# Strampler_redesign_v2_2.net
KiCad netlist of a schematic drawn in EAGLE
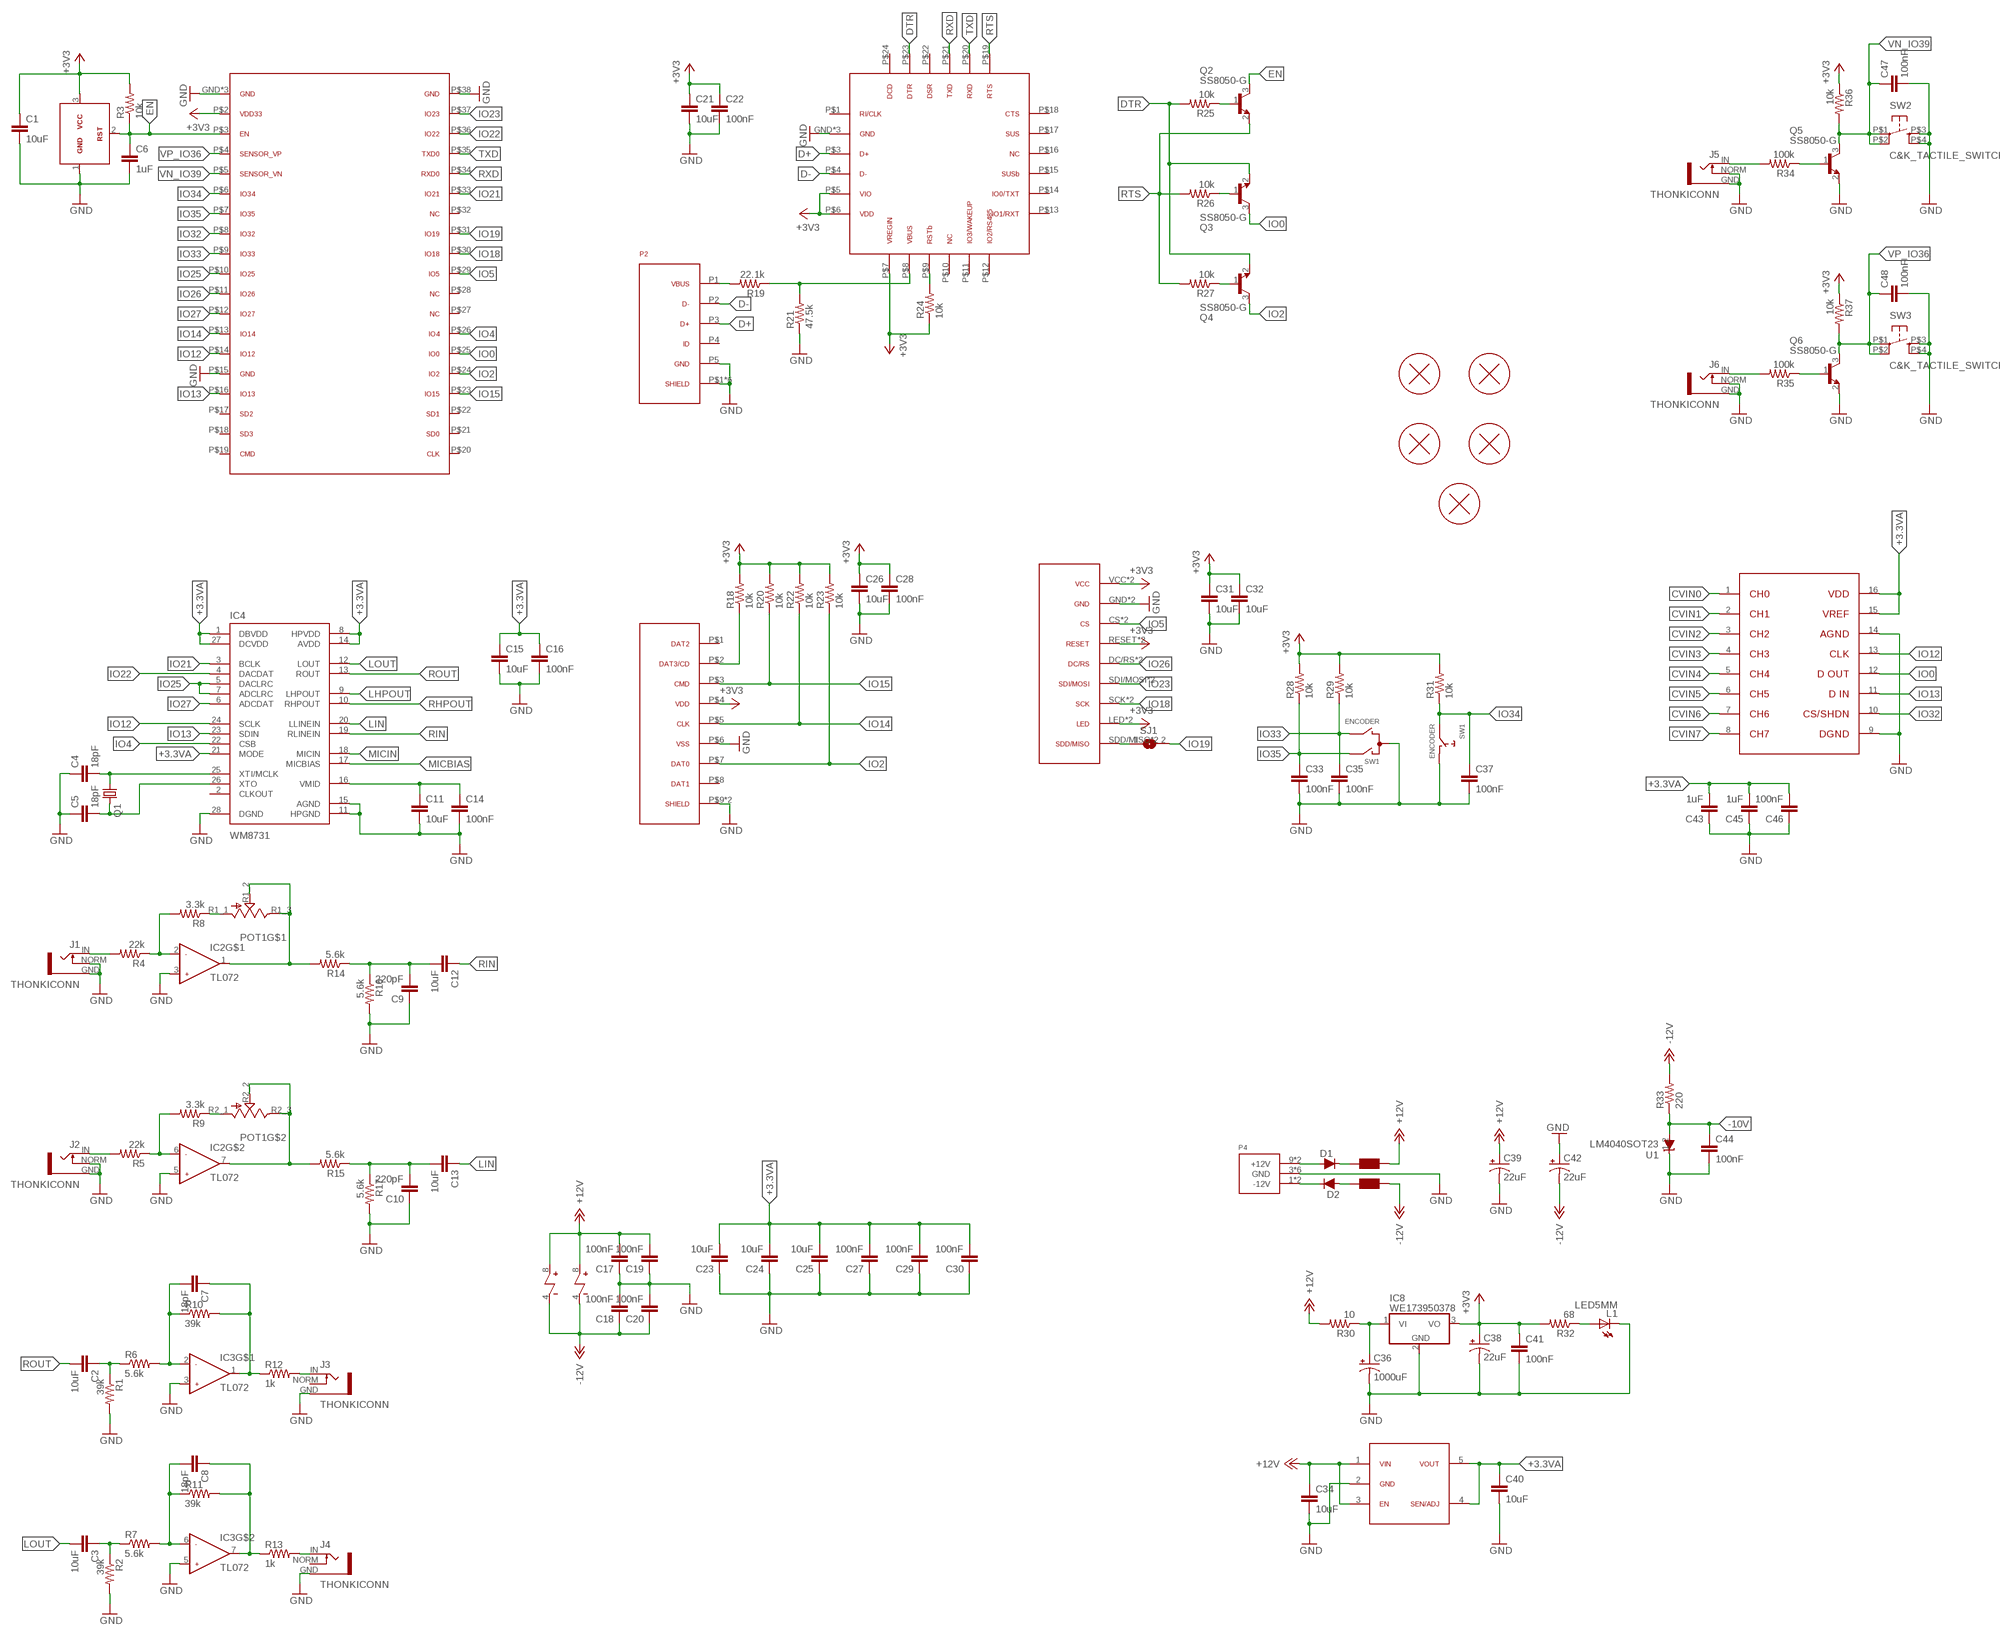
[diagram p0: schematic, sheet 1, part 1 of 2]
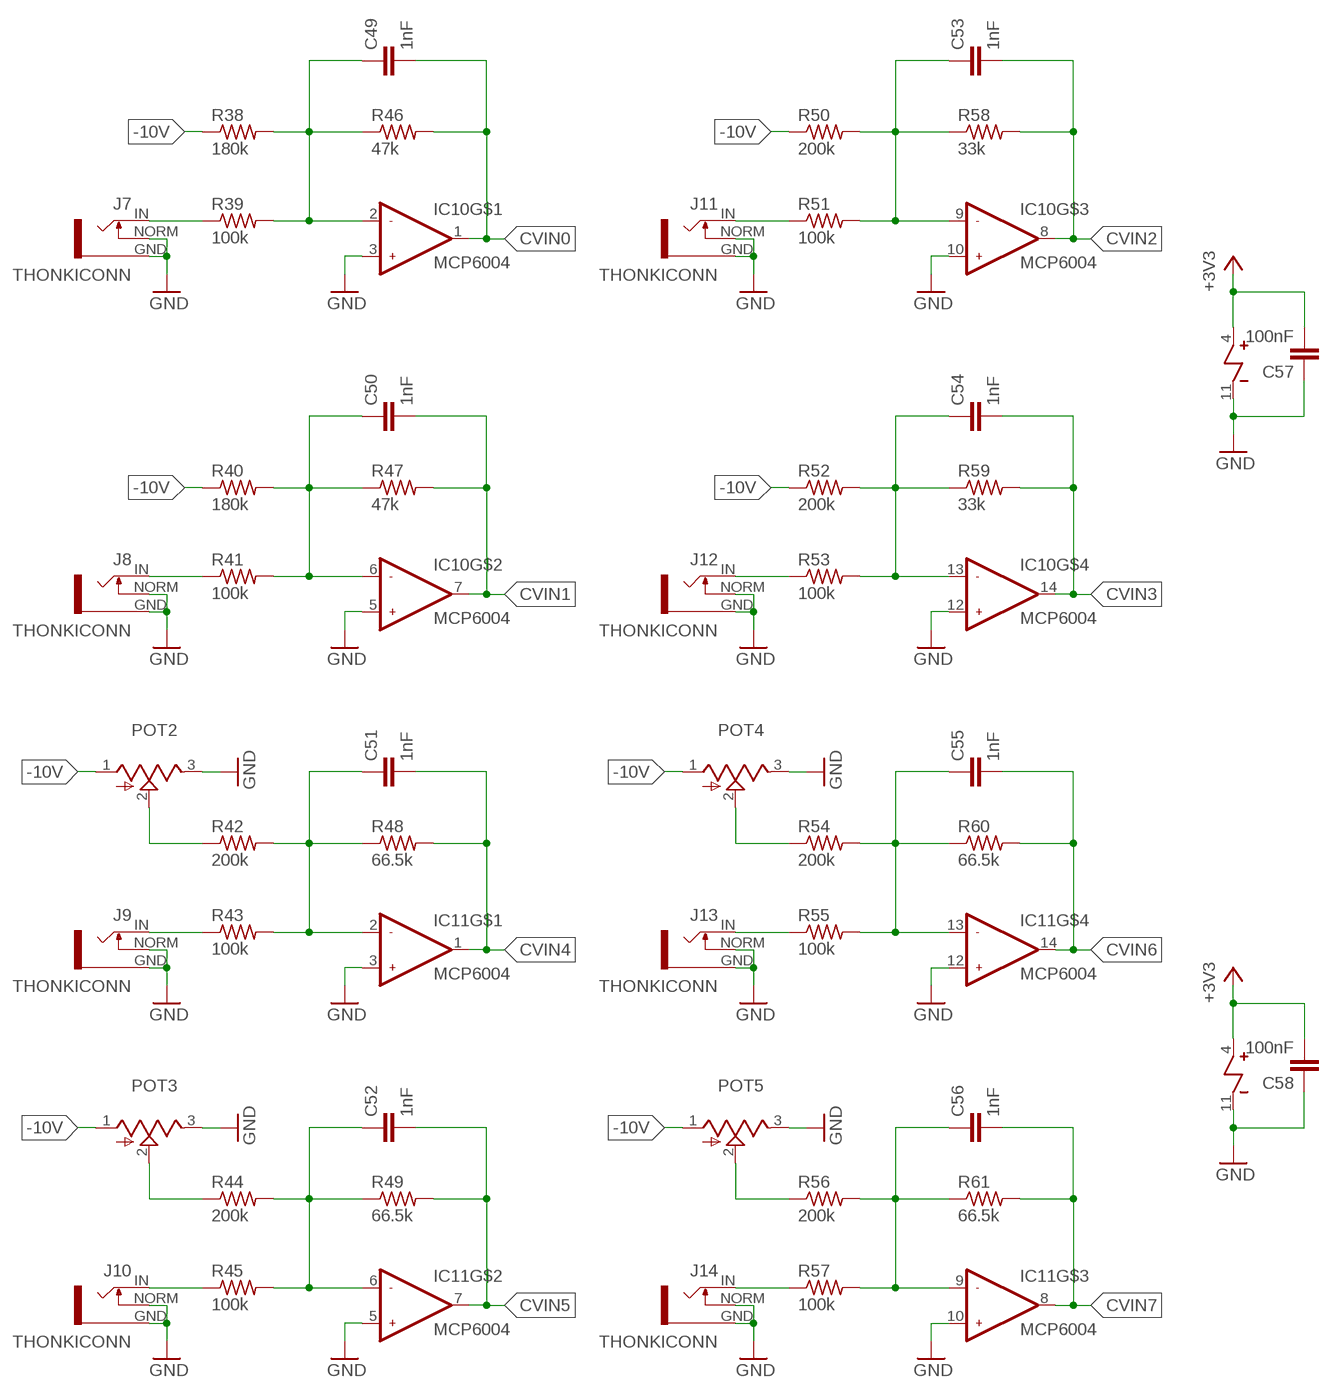
[diagram p1: schematic, sheet 1, part 2 of 2]

(export (version "E")
  (design (tool "Eeschema 10.0.6"))
  (components
    (comp (ref "C1")
      (value "10uF")
      (footprint "eagle-import:R0805")
      (libsource (lib "eagle-import") (part "CAPACITOR0805"))
    )
    (comp (ref "C2")
      (value "10uF")
      (footprint "eagle-import:R0805")
      (libsource (lib "eagle-import") (part "CAPACITOR0805"))
    )
    (comp (ref "C3")
      (value "10uF")
      (footprint "eagle-import:R0805")
      (libsource (lib "eagle-import") (part "CAPACITOR0805"))
    )
    (comp (ref "C4")
      (value "18pF")
      (footprint "eagle-import:RESISTOR_0603")
      (libsource (lib "eagle-import") (part "CAPACITOR"))
    )
    (comp (ref "C5")
      (value "18pF")
      (footprint "eagle-import:RESISTOR_0603")
      (libsource (lib "eagle-import") (part "CAPACITOR"))
    )
    (comp (ref "C6")
      (value "1uF")
      (footprint "eagle-import:RESISTOR_0603")
      (libsource (lib "eagle-import") (part "CAPACITOR"))
    )
    (comp (ref "C7")
      (value "18pF")
      (footprint "eagle-import:RESISTOR_0603")
      (libsource (lib "eagle-import") (part "CAPACITOR"))
    )
    (comp (ref "C8")
      (value "18pF")
      (footprint "eagle-import:RESISTOR_0603")
      (libsource (lib "eagle-import") (part "CAPACITOR"))
    )
    (comp (ref "C9")
      (value "220pF")
      (footprint "eagle-import:RESISTOR_0603")
      (libsource (lib "eagle-import") (part "CAPACITOR"))
    )
    (comp (ref "C10")
      (value "220pF")
      (footprint "eagle-import:RESISTOR_0603")
      (libsource (lib "eagle-import") (part "CAPACITOR"))
    )
    (comp (ref "C11")
      (value "10uF")
      (footprint "eagle-import:R0805")
      (libsource (lib "eagle-import") (part "CAPACITOR0805"))
    )
    (comp (ref "C12")
      (value "10uF")
      (footprint "eagle-import:R0805")
      (libsource (lib "eagle-import") (part "CAPACITOR0805"))
    )
    (comp (ref "C13")
      (value "10uF")
      (footprint "eagle-import:R0805")
      (libsource (lib "eagle-import") (part "CAPACITOR0805"))
    )
    (comp (ref "C14")
      (value "100nF")
      (footprint "eagle-import:RESISTOR_0603")
      (libsource (lib "eagle-import") (part "CAPACITOR"))
    )
    (comp (ref "C15")
      (value "10uF")
      (footprint "eagle-import:R0805")
      (libsource (lib "eagle-import") (part "CAPACITOR0805"))
    )
    (comp (ref "C16")
      (value "100nF")
      (footprint "eagle-import:RESISTOR_0603")
      (libsource (lib "eagle-import") (part "CAPACITOR"))
    )
    (comp (ref "C17")
      (value "100nF")
      (footprint "eagle-import:RESISTOR_0603")
      (libsource (lib "eagle-import") (part "CAPACITOR"))
    )
    (comp (ref "C18")
      (value "100nF")
      (footprint "eagle-import:RESISTOR_0603")
      (libsource (lib "eagle-import") (part "CAPACITOR"))
    )
    (comp (ref "C19")
      (value "100nF")
      (footprint "eagle-import:RESISTOR_0603")
      (libsource (lib "eagle-import") (part "CAPACITOR"))
    )
    (comp (ref "C20")
      (value "100nF")
      (footprint "eagle-import:RESISTOR_0603")
      (libsource (lib "eagle-import") (part "CAPACITOR"))
    )
    (comp (ref "C21")
      (value "10uF")
      (footprint "eagle-import:R0805")
      (libsource (lib "eagle-import") (part "CAPACITOR0805"))
    )
    (comp (ref "C22")
      (value "100nF")
      (footprint "eagle-import:RESISTOR_0603")
      (libsource (lib "eagle-import") (part "CAPACITOR"))
    )
    (comp (ref "C23")
      (value "10uF")
      (footprint "eagle-import:R0805")
      (libsource (lib "eagle-import") (part "CAPACITOR0805"))
    )
    (comp (ref "C24")
      (value "10uF")
      (footprint "eagle-import:R0805")
      (libsource (lib "eagle-import") (part "CAPACITOR0805"))
    )
    (comp (ref "C25")
      (value "10uF")
      (footprint "eagle-import:R0805")
      (libsource (lib "eagle-import") (part "CAPACITOR0805"))
    )
    (comp (ref "C26")
      (value "10uF")
      (footprint "eagle-import:R0805")
      (libsource (lib "eagle-import") (part "CAPACITOR0805"))
    )
    (comp (ref "C27")
      (value "100nF")
      (footprint "eagle-import:RESISTOR_0603")
      (libsource (lib "eagle-import") (part "CAPACITOR"))
    )
    (comp (ref "C28")
      (value "100nF")
      (footprint "eagle-import:RESISTOR_0603")
      (libsource (lib "eagle-import") (part "CAPACITOR"))
    )
    (comp (ref "C29")
      (value "100nF")
      (footprint "eagle-import:RESISTOR_0603")
      (libsource (lib "eagle-import") (part "CAPACITOR"))
    )
    (comp (ref "C30")
      (value "100nF")
      (footprint "eagle-import:RESISTOR_0603")
      (libsource (lib "eagle-import") (part "CAPACITOR"))
    )
    (comp (ref "C31")
      (value "10uF")
      (footprint "eagle-import:R0805")
      (libsource (lib "eagle-import") (part "CAPACITOR0805"))
    )
    (comp (ref "C32")
      (value "10uF")
      (footprint "eagle-import:R0805")
      (libsource (lib "eagle-import") (part "CAPACITOR0805"))
    )
    (comp (ref "C33")
      (value "100nF")
      (footprint "eagle-import:RESISTOR_0603")
      (libsource (lib "eagle-import") (part "CAPACITOR"))
    )
    (comp (ref "C34")
      (value "10uF")
      (footprint "eagle-import:R1210")
      (libsource (lib "eagle-import") (part "CAPACITOR1210"))
    )
    (comp (ref "C35")
      (value "100nF")
      (footprint "eagle-import:RESISTOR_0603")
      (libsource (lib "eagle-import") (part "CAPACITOR"))
    )
    (comp (ref "C36")
      (value "1000uF")
      (footprint "eagle-import:PANASONIC_G")
      (libsource (lib "eagle-import") (part "CAP_POLG"))
    )
    (comp (ref "C37")
      (value "100nF")
      (footprint "eagle-import:RESISTOR_0603")
      (libsource (lib "eagle-import") (part "CAPACITOR"))
    )
    (comp (ref "C38")
      (value "22uF")
      (footprint "eagle-import:1206_POL")
      (libsource (lib "eagle-import") (part "CAP_POL1206_TANT"))
    )
    (comp (ref "C39")
      (value "22uF")
      (footprint "eagle-import:1206_POL")
      (libsource (lib "eagle-import") (part "CAP_POL1206_TANT"))
    )
    (comp (ref "C40")
      (value "10uF")
      (footprint "eagle-import:R0805")
      (libsource (lib "eagle-import") (part "CAPACITOR0805"))
    )
    (comp (ref "C41")
      (value "100nF")
      (footprint "eagle-import:RESISTOR_0603")
      (libsource (lib "eagle-import") (part "CAPACITOR"))
    )
    (comp (ref "C42")
      (value "22uF")
      (footprint "eagle-import:1206_POL")
      (libsource (lib "eagle-import") (part "CAP_POL1206_TANT"))
    )
    (comp (ref "C43")
      (value "1uF")
      (footprint "eagle-import:RESISTOR_0603")
      (libsource (lib "eagle-import") (part "CAPACITOR"))
    )
    (comp (ref "C44")
      (value "100nF")
      (footprint "eagle-import:RESISTOR_0603")
      (libsource (lib "eagle-import") (part "CAPACITOR"))
    )
    (comp (ref "C45")
      (value "1uF")
      (footprint "eagle-import:RESISTOR_0603")
      (libsource (lib "eagle-import") (part "CAPACITOR"))
    )
    (comp (ref "C46")
      (value "100nF")
      (footprint "eagle-import:RESISTOR_0603")
      (libsource (lib "eagle-import") (part "CAPACITOR"))
    )
    (comp (ref "C47")
      (value "100nF")
      (footprint "eagle-import:RESISTOR_0603")
      (libsource (lib "eagle-import") (part "CAPACITOR"))
    )
    (comp (ref "C48")
      (value "100nF")
      (footprint "eagle-import:RESISTOR_0603")
      (libsource (lib "eagle-import") (part "CAPACITOR"))
    )
    (comp (ref "C49")
      (value "1nF")
      (footprint "eagle-import:RESISTOR_0603")
      (libsource (lib "eagle-import") (part "CAPACITOR"))
    )
    (comp (ref "C50")
      (value "1nF")
      (footprint "eagle-import:RESISTOR_0603")
      (libsource (lib "eagle-import") (part "CAPACITOR"))
    )
    (comp (ref "C51")
      (value "1nF")
      (footprint "eagle-import:RESISTOR_0603")
      (libsource (lib "eagle-import") (part "CAPACITOR"))
    )
    (comp (ref "C52")
      (value "1nF")
      (footprint "eagle-import:RESISTOR_0603")
      (libsource (lib "eagle-import") (part "CAPACITOR"))
    )
    (comp (ref "C53")
      (value "1nF")
      (footprint "eagle-import:RESISTOR_0603")
      (libsource (lib "eagle-import") (part "CAPACITOR"))
    )
    (comp (ref "C54")
      (value "1nF")
      (footprint "eagle-import:RESISTOR_0603")
      (libsource (lib "eagle-import") (part "CAPACITOR"))
    )
    (comp (ref "C55")
      (value "1nF")
      (footprint "eagle-import:RESISTOR_0603")
      (libsource (lib "eagle-import") (part "CAPACITOR"))
    )
    (comp (ref "C56")
      (value "1nF")
      (footprint "eagle-import:RESISTOR_0603")
      (libsource (lib "eagle-import") (part "CAPACITOR"))
    )
    (comp (ref "C57")
      (value "100nF")
      (footprint "eagle-import:RESISTOR_0603")
      (libsource (lib "eagle-import") (part "CAPACITOR"))
    )
    (comp (ref "C58")
      (value "100nF")
      (footprint "eagle-import:RESISTOR_0603")
      (libsource (lib "eagle-import") (part "CAPACITOR"))
    )
    (comp (ref "D1")
      (value "DIODE")
      (footprint "eagle-import:SOD123")
      (libsource (lib "eagle-import") (part "DIODE"))
    )
    (comp (ref "D2")
      (value "DIODE")
      (footprint "eagle-import:SOD123")
      (libsource (lib "eagle-import") (part "DIODE"))
    )
    (comp (ref "F1")
      (value "FERRITE-BEAD0805")
      (footprint "eagle-import:R0805")
      (libsource (lib "eagle-import") (part "FERRITE-BEAD0805"))
    )
    (comp (ref "F2")
      (value "FERRITE-BEAD0805")
      (footprint "eagle-import:R0805")
      (libsource (lib "eagle-import") (part "FERRITE-BEAD0805"))
    )
    (comp (ref "H1")
      (value "PCB_SCREW")
      (footprint "eagle-import:PCB_SCREW")
      (libsource (lib "eagle-import") (part "PCB_SCREW"))
    )
    (comp (ref "H2")
      (value "PCB_SCREW")
      (footprint "eagle-import:PCB_SCREW")
      (libsource (lib "eagle-import") (part "PCB_SCREW"))
    )
    (comp (ref "H3")
      (value "PCB_SCREW")
      (footprint "eagle-import:PCB_SCREW")
      (libsource (lib "eagle-import") (part "PCB_SCREW"))
    )
    (comp (ref "H4")
      (value "PCB_SCREW")
      (footprint "eagle-import:PCB_SCREW")
      (libsource (lib "eagle-import") (part "PCB_SCREW"))
    )
    (comp (ref "H5")
      (value "PCB_SCREW")
      (footprint "eagle-import:PCB_SCREW")
      (libsource (lib "eagle-import") (part "PCB_SCREW"))
    )
    (comp (ref "IC1")
      (value "MIC803")
      (footprint "eagle-import:SOT23")
      (libsource (lib "eagle-import") (part "MIC803"))
    )
    (comp (ref "IC2")
      (value "TL072")
      (footprint "eagle-import:SOIC8")
      (libsource (lib "eagle-import") (part "OPAMP_DUAL"))
    )
    (comp (ref "IC3")
      (value "TL072")
      (footprint "eagle-import:SOIC8")
      (libsource (lib "eagle-import") (part "OPAMP_DUAL"))
    )
    (comp (ref "IC4")
      (value "WM8731")
      (footprint "eagle-import:SSOP28")
      (libsource (lib "eagle-import") (part "WM8731"))
    )
    (comp (ref "IC5")
      (value "ESP32-WROVER-B")
      (footprint "eagle-import:ESP32-WROVER-B")
      (libsource (lib "eagle-import") (part "ESP32-WROVER-B"))
    )
    (comp (ref "IC6")
      (value "CP2102N")
      (footprint "eagle-import:CP2102N")
      (libsource (lib "eagle-import") (part "CP2102N"))
    )
    (comp (ref "IC7")
      (value "ADP7118")
      (footprint "eagle-import:SOT23-5L")
      (libsource (lib "eagle-import") (part "ADP7118"))
    )
    (comp (ref "IC8")
      (value "WE173950378")
      (footprint "eagle-import:WE78")
      (libsource (lib "eagle-import") (part "WE173950378"))
    )
    (comp (ref "IC9")
      (value "MCP3208")
      (footprint "eagle-import:SOIC16")
      (libsource (lib "eagle-import") (part "MCP3208"))
    )
    (comp (ref "IC10")
      (value "MCP6004")
      (footprint "eagle-import:TSSOP14")
      (libsource (lib "eagle-import") (part "OPAMP_QUADPWR"))
    )
    (comp (ref "IC11")
      (value "MCP6004")
      (footprint "eagle-import:TSSOP14")
      (libsource (lib "eagle-import") (part "OPAMP_QUADPWR"))
    )
    (comp (ref "J1")
      (value "THONKICONN")
      (footprint "eagle-import:PROTOJACK")
      (libsource (lib "eagle-import") (part "THONKICONN"))
    )
    (comp (ref "J2")
      (value "THONKICONN")
      (footprint "eagle-import:PROTOJACK")
      (libsource (lib "eagle-import") (part "THONKICONN"))
    )
    (comp (ref "J3")
      (value "THONKICONN")
      (footprint "eagle-import:PROTOJACK")
      (libsource (lib "eagle-import") (part "THONKICONN"))
    )
    (comp (ref "J4")
      (value "THONKICONN")
      (footprint "eagle-import:PROTOJACK")
      (libsource (lib "eagle-import") (part "THONKICONN"))
    )
    (comp (ref "J5")
      (value "THONKICONN")
      (footprint "eagle-import:PROTOJACK")
      (libsource (lib "eagle-import") (part "THONKICONN"))
    )
    (comp (ref "J6")
      (value "THONKICONN")
      (footprint "eagle-import:PROTOJACK")
      (libsource (lib "eagle-import") (part "THONKICONN"))
    )
    (comp (ref "J7")
      (value "THONKICONN")
      (footprint "eagle-import:PROTOJACK")
      (libsource (lib "eagle-import") (part "THONKICONN"))
    )
    (comp (ref "J8")
      (value "THONKICONN")
      (footprint "eagle-import:PROTOJACK")
      (libsource (lib "eagle-import") (part "THONKICONN"))
    )
    (comp (ref "J9")
      (value "THONKICONN")
      (footprint "eagle-import:PROTOJACK")
      (libsource (lib "eagle-import") (part "THONKICONN"))
    )
    (comp (ref "J10")
      (value "THONKICONN")
      (footprint "eagle-import:PROTOJACK")
      (libsource (lib "eagle-import") (part "THONKICONN"))
    )
    (comp (ref "J11")
      (value "THONKICONN")
      (footprint "eagle-import:PROTOJACK")
      (libsource (lib "eagle-import") (part "THONKICONN"))
    )
    (comp (ref "J12")
      (value "THONKICONN")
      (footprint "eagle-import:PROTOJACK")
      (libsource (lib "eagle-import") (part "THONKICONN"))
    )
    (comp (ref "J13")
      (value "THONKICONN")
      (footprint "eagle-import:PROTOJACK")
      (libsource (lib "eagle-import") (part "THONKICONN"))
    )
    (comp (ref "J14")
      (value "THONKICONN")
      (footprint "eagle-import:PROTOJACK")
      (libsource (lib "eagle-import") (part "THONKICONN"))
    )
    (comp (ref "L1")
      (value "LED5MM")
      (footprint "eagle-import:LED_5MM")
      (libsource (lib "eagle-import") (part "LED5MM"))
    )
    (comp (ref "P1")
      (value "SD-CARD")
      (footprint "eagle-import:SD-CARD-THONK")
      (libsource (lib "eagle-import") (part "SD-CARD"))
    )
    (comp (ref "P2")
      (value "USB-B")
      (footprint "eagle-import:USB-B-MOLEX-1050170001")
      (libsource (lib "eagle-import") (part "USB-B"))
    )
    (comp (ref "P3")
      (value "MSP2202_DISPLAY")
      (footprint "eagle-import:MSP2202_DISPLAY")
      (libsource (lib "eagle-import") (part "MSP2202_DISPLAY"))
    )
    (comp (ref "P4")
      (value "POWER_SIMPLE10")
      (footprint "eagle-import:POWER_10")
      (libsource (lib "eagle-import") (part "POWER_SIMPLE10"))
    )
    (comp (ref "POT1")
      (value "POT_DUAL_THONK")
      (footprint "eagle-import:POT_DUAL_THONK")
      (libsource (lib "eagle-import") (part "POT_DUAL_THONK"))
    )
    (comp (ref "POT2")
      (value "POT_VERTICAL")
      (footprint "eagle-import:ALPS_POT_VERTICAL")
      (libsource (lib "eagle-import") (part "POT_VERTICAL"))
    )
    (comp (ref "POT3")
      (value "POT_VERTICAL")
      (footprint "eagle-import:ALPS_POT_VERTICAL")
      (libsource (lib "eagle-import") (part "POT_VERTICAL"))
    )
    (comp (ref "POT4")
      (value "POT_VERTICAL")
      (footprint "eagle-import:ALPS_POT_VERTICAL")
      (libsource (lib "eagle-import") (part "POT_VERTICAL"))
    )
    (comp (ref "POT5")
      (value "POT_VERTICAL")
      (footprint "eagle-import:ALPS_POT_VERTICAL")
      (libsource (lib "eagle-import") (part "POT_VERTICAL"))
    )
    (comp (ref "Q1")
      (value "CRYSTAL")
      (footprint "eagle-import:HC49UP")
      (libsource (lib "eagle-import") (part "CRYSTAL"))
    )
    (comp (ref "Q2")
      (value "SS8050-G")
      (footprint "eagle-import:SOT23")
      (libsource (lib "eagle-import") (part "MMBT3904SOT23"))
    )
    (comp (ref "Q3")
      (value "SS8050-G")
      (footprint "eagle-import:SOT23")
      (libsource (lib "eagle-import") (part "MMBT3904SOT23"))
    )
    (comp (ref "Q4")
      (value "SS8050-G")
      (footprint "eagle-import:SOT23")
      (libsource (lib "eagle-import") (part "MMBT3904SOT23"))
    )
    (comp (ref "Q5")
      (value "SS8050-G")
      (footprint "eagle-import:SOT23")
      (libsource (lib "eagle-import") (part "MMBT3904SOT23"))
    )
    (comp (ref "Q6")
      (value "SS8050-G")
      (footprint "eagle-import:SOT23")
      (libsource (lib "eagle-import") (part "MMBT3904SOT23"))
    )
    (comp (ref "R1")
      (value "39k")
      (footprint "eagle-import:RESISTOR_0603")
      (libsource (lib "eagle-import") (part "RESISTOR"))
    )
    (comp (ref "R2")
      (value "39k")
      (footprint "eagle-import:RESISTOR_0603")
      (libsource (lib "eagle-import") (part "RESISTOR"))
    )
    (comp (ref "R3")
      (value "10k")
      (footprint "eagle-import:RESISTOR_0603")
      (libsource (lib "eagle-import") (part "RESISTOR"))
    )
    (comp (ref "R4")
      (value "22k")
      (footprint "eagle-import:RESISTOR_0603")
      (libsource (lib "eagle-import") (part "RESISTOR"))
    )
    (comp (ref "R5")
      (value "22k")
      (footprint "eagle-import:RESISTOR_0603")
      (libsource (lib "eagle-import") (part "RESISTOR"))
    )
    (comp (ref "R6")
      (value "5.6k")
      (footprint "eagle-import:RESISTOR_0603")
      (libsource (lib "eagle-import") (part "RESISTOR"))
    )
    (comp (ref "R7")
      (value "5.6k")
      (footprint "eagle-import:RESISTOR_0603")
      (libsource (lib "eagle-import") (part "RESISTOR"))
    )
    (comp (ref "R8")
      (value "3.3k")
      (footprint "eagle-import:RESISTOR_0603")
      (libsource (lib "eagle-import") (part "RESISTOR"))
    )
    (comp (ref "R9")
      (value "3.3k")
      (footprint "eagle-import:RESISTOR_0603")
      (libsource (lib "eagle-import") (part "RESISTOR"))
    )
    (comp (ref "R10")
      (value "39k")
      (footprint "eagle-import:RESISTOR_0603")
      (libsource (lib "eagle-import") (part "RESISTOR"))
    )
    (comp (ref "R11")
      (value "39k")
      (footprint "eagle-import:RESISTOR_0603")
      (libsource (lib "eagle-import") (part "RESISTOR"))
    )
    (comp (ref "R12")
      (value "1k")
      (footprint "eagle-import:RESISTOR_0603")
      (libsource (lib "eagle-import") (part "RESISTOR"))
    )
    (comp (ref "R13")
      (value "1k")
      (footprint "eagle-import:RESISTOR_0603")
      (libsource (lib "eagle-import") (part "RESISTOR"))
    )
    (comp (ref "R14")
      (value "5.6k")
      (footprint "eagle-import:RESISTOR_0603")
      (libsource (lib "eagle-import") (part "RESISTOR"))
    )
    (comp (ref "R15")
      (value "5.6k")
      (footprint "eagle-import:RESISTOR_0603")
      (libsource (lib "eagle-import") (part "RESISTOR"))
    )
    (comp (ref "R16")
      (value "5.6k")
      (footprint "eagle-import:RESISTOR_0603")
      (libsource (lib "eagle-import") (part "RESISTOR"))
    )
    (comp (ref "R17")
      (value "5.6k")
      (footprint "eagle-import:RESISTOR_0603")
      (libsource (lib "eagle-import") (part "RESISTOR"))
    )
    (comp (ref "R18")
      (value "10k")
      (footprint "eagle-import:RESISTOR_0603")
      (libsource (lib "eagle-import") (part "RESISTOR"))
    )
    (comp (ref "R19")
      (value "22.1k")
      (footprint "eagle-import:RESISTOR_0603")
      (libsource (lib "eagle-import") (part "RESISTOR"))
    )
    (comp (ref "R20")
      (value "10k")
      (footprint "eagle-import:RESISTOR_0603")
      (libsource (lib "eagle-import") (part "RESISTOR"))
    )
    (comp (ref "R21")
      (value "47.5k")
      (footprint "eagle-import:RESISTOR_0603")
      (libsource (lib "eagle-import") (part "RESISTOR"))
    )
    (comp (ref "R22")
      (value "10k")
      (footprint "eagle-import:RESISTOR_0603")
      (libsource (lib "eagle-import") (part "RESISTOR"))
    )
    (comp (ref "R23")
      (value "10k")
      (footprint "eagle-import:RESISTOR_0603")
      (libsource (lib "eagle-import") (part "RESISTOR"))
    )
    (comp (ref "R24")
      (value "10k")
      (footprint "eagle-import:RESISTOR_0603")
      (libsource (lib "eagle-import") (part "RESISTOR"))
    )
    (comp (ref "R25")
      (value "10k")
      (footprint "eagle-import:RESISTOR_0603")
      (libsource (lib "eagle-import") (part "RESISTOR"))
    )
    (comp (ref "R26")
      (value "10k")
      (footprint "eagle-import:RESISTOR_0603")
      (libsource (lib "eagle-import") (part "RESISTOR"))
    )
    (comp (ref "R27")
      (value "10k")
      (footprint "eagle-import:RESISTOR_0603")
      (libsource (lib "eagle-import") (part "RESISTOR"))
    )
    (comp (ref "R28")
      (value "10k")
      (footprint "eagle-import:RESISTOR_0603")
      (libsource (lib "eagle-import") (part "RESISTOR"))
    )
    (comp (ref "R29")
      (value "10k")
      (footprint "eagle-import:RESISTOR_0603")
      (libsource (lib "eagle-import") (part "RESISTOR"))
    )
    (comp (ref "R30")
      (value "10")
      (footprint "eagle-import:R2512")
      (libsource (lib "eagle-import") (part "RESISTOR2512"))
    )
    (comp (ref "R31")
      (value "10k")
      (footprint "eagle-import:RESISTOR_0603")
      (libsource (lib "eagle-import") (part "RESISTOR"))
    )
    (comp (ref "R32")
      (value "68")
      (footprint "eagle-import:RESISTOR_0603")
      (libsource (lib "eagle-import") (part "RESISTOR"))
    )
    (comp (ref "R33")
      (value "220")
      (footprint "eagle-import:RESISTOR_0603")
      (libsource (lib "eagle-import") (part "RESISTOR"))
    )
    (comp (ref "R34")
      (value "100k")
      (footprint "eagle-import:RESISTOR_0603")
      (libsource (lib "eagle-import") (part "RESISTOR"))
    )
    (comp (ref "R35")
      (value "100k")
      (footprint "eagle-import:RESISTOR_0603")
      (libsource (lib "eagle-import") (part "RESISTOR"))
    )
    (comp (ref "R36")
      (value "10k")
      (footprint "eagle-import:RESISTOR_0603")
      (libsource (lib "eagle-import") (part "RESISTOR"))
    )
    (comp (ref "R37")
      (value "10k")
      (footprint "eagle-import:RESISTOR_0603")
      (libsource (lib "eagle-import") (part "RESISTOR"))
    )
    (comp (ref "R38")
      (value "180k")
      (footprint "eagle-import:RESISTOR_0603")
      (libsource (lib "eagle-import") (part "RESISTOR"))
    )
    (comp (ref "R39")
      (value "100k")
      (footprint "eagle-import:RESISTOR_0603")
      (libsource (lib "eagle-import") (part "RESISTOR"))
    )
    (comp (ref "R40")
      (value "180k")
      (footprint "eagle-import:RESISTOR_0603")
      (libsource (lib "eagle-import") (part "RESISTOR"))
    )
    (comp (ref "R41")
      (value "100k")
      (footprint "eagle-import:RESISTOR_0603")
      (libsource (lib "eagle-import") (part "RESISTOR"))
    )
    (comp (ref "R42")
      (value "200k")
      (footprint "eagle-import:RESISTOR_0603")
      (libsource (lib "eagle-import") (part "RESISTOR"))
    )
    (comp (ref "R43")
      (value "100k")
      (footprint "eagle-import:RESISTOR_0603")
      (libsource (lib "eagle-import") (part "RESISTOR"))
    )
    (comp (ref "R44")
      (value "200k")
      (footprint "eagle-import:RESISTOR_0603")
      (libsource (lib "eagle-import") (part "RESISTOR"))
    )
    (comp (ref "R45")
      (value "100k")
      (footprint "eagle-import:RESISTOR_0603")
      (libsource (lib "eagle-import") (part "RESISTOR"))
    )
    (comp (ref "R46")
      (value "47k")
      (footprint "eagle-import:RESISTOR_0603")
      (libsource (lib "eagle-import") (part "RESISTOR"))
    )
    (comp (ref "R47")
      (value "47k")
      (footprint "eagle-import:RESISTOR_0603")
      (libsource (lib "eagle-import") (part "RESISTOR"))
    )
    (comp (ref "R48")
      (value "66.5k")
      (footprint "eagle-import:RESISTOR_0603")
      (libsource (lib "eagle-import") (part "RESISTOR"))
    )
    (comp (ref "R49")
      (value "66.5k")
      (footprint "eagle-import:RESISTOR_0603")
      (libsource (lib "eagle-import") (part "RESISTOR"))
    )
    (comp (ref "R50")
      (value "200k")
      (footprint "eagle-import:RESISTOR_0603")
      (libsource (lib "eagle-import") (part "RESISTOR"))
    )
    (comp (ref "R51")
      (value "100k")
      (footprint "eagle-import:RESISTOR_0603")
      (libsource (lib "eagle-import") (part "RESISTOR"))
    )
    (comp (ref "R52")
      (value "200k")
      (footprint "eagle-import:RESISTOR_0603")
      (libsource (lib "eagle-import") (part "RESISTOR"))
    )
    (comp (ref "R53")
      (value "100k")
      (footprint "eagle-import:RESISTOR_0603")
      (libsource (lib "eagle-import") (part "RESISTOR"))
    )
    (comp (ref "R54")
      (value "200k")
      (footprint "eagle-import:RESISTOR_0603")
      (libsource (lib "eagle-import") (part "RESISTOR"))
    )
    (comp (ref "R55")
      (value "100k")
      (footprint "eagle-import:RESISTOR_0603")
      (libsource (lib "eagle-import") (part "RESISTOR"))
    )
    (comp (ref "R56")
      (value "200k")
      (footprint "eagle-import:RESISTOR_0603")
      (libsource (lib "eagle-import") (part "RESISTOR"))
    )
    (comp (ref "R57")
      (value "100k")
      (footprint "eagle-import:RESISTOR_0603")
      (libsource (lib "eagle-import") (part "RESISTOR"))
    )
    (comp (ref "R58")
      (value "33k")
      (footprint "eagle-import:RESISTOR_0603")
      (libsource (lib "eagle-import") (part "RESISTOR"))
    )
    (comp (ref "R59")
      (value "33k")
      (footprint "eagle-import:RESISTOR_0603")
      (libsource (lib "eagle-import") (part "RESISTOR"))
    )
    (comp (ref "R60")
      (value "66.5k")
      (footprint "eagle-import:RESISTOR_0603")
      (libsource (lib "eagle-import") (part "RESISTOR"))
    )
    (comp (ref "R61")
      (value "66.5k")
      (footprint "eagle-import:RESISTOR_0603")
      (libsource (lib "eagle-import") (part "RESISTOR"))
    )
    (comp (ref "SJ1") (value "SJ") (footprint "eagle-import:SJ") (libsource (lib "eagle-import") (part "SJ")))
    (comp (ref "SW1")
      (value "ENCODER")
      (footprint "eagle-import:ALPS_EC12E_SW")
      (fields (field (name "MPN") "EC12E2424407"))
      (libsource (lib "eagle-import") (part "ENCODER"))
    )
    (comp (ref "SW2")
      (value "C&K_TACTILE_SWITCH")
      (footprint "eagle-import:C&K_TACTILE_SWITCH")
      (libsource (lib "eagle-import") (part "C&K_TACTILE_SWITCH"))
    )
    (comp (ref "SW3")
      (value "C&K_TACTILE_SWITCH")
      (footprint "eagle-import:C&K_TACTILE_SWITCH")
      (libsource (lib "eagle-import") (part "C&K_TACTILE_SWITCH"))
    )
    (comp (ref "U1")
      (value "LM4040SOT23")
      (footprint "eagle-import:SOT23")
      (libsource (lib "eagle-import") (part "LM4040SOT23"))
    )
  )
  (nets
    (net (code "1") (name "+3.3VA") (class "Default")
      (node (ref "C15") (pin "1") (pinfunction "1_1") (pintype "passive"))
      (node (ref "C16") (pin "1") (pinfunction "1_1") (pintype "passive"))
      (node (ref "C23") (pin "2") (pinfunction "2_2") (pintype "passive"))
      (node (ref "C24") (pin "2") (pinfunction "2_2") (pintype "passive"))
      (node (ref "C25") (pin "2") (pinfunction "2_2") (pintype "passive"))
      (node (ref "C27") (pin "2") (pinfunction "2_2") (pintype "passive"))
      (node (ref "C29") (pin "2") (pinfunction "2_2") (pintype "passive"))
      (node (ref "C30") (pin "2") (pinfunction "2_2") (pintype "passive"))
      (node (ref "C40") (pin "1") (pinfunction "1_1") (pintype "passive"))
      (node (ref "C43") (pin "2") (pinfunction "2_2") (pintype "passive"))
      (node (ref "C45") (pin "2") (pinfunction "2_2") (pintype "passive"))
      (node (ref "C46") (pin "2") (pinfunction "2_2") (pintype "passive"))
      (node (ref "IC4") (pin "1") (pinfunction "DBVDD_1") (pintype "bidirectional"))
      (node (ref "IC4") (pin "14") (pinfunction "AVDD_14") (pintype "bidirectional"))
      (node (ref "IC4") (pin "21") (pinfunction "MODE_21") (pintype "bidirectional"))
      (node (ref "IC4") (pin "27") (pinfunction "DCVDD_27") (pintype "bidirectional"))
      (node (ref "IC4") (pin "8") (pinfunction "HPVDD_8") (pintype "bidirectional"))
      (node (ref "IC7") (pin "4") (pinfunction "P$4_4") (pintype "bidirectional"))
      (node (ref "IC7") (pin "5") (pinfunction "P$5_5") (pintype "bidirectional"))
      (node (ref "IC9") (pin "15") (pinfunction "P$15_15") (pintype "bidirectional"))
      (node (ref "IC9") (pin "16") (pinfunction "P$16_16") (pintype "bidirectional"))
    )
    (net (code "2") (name "+3V3") (class "Default")
      (node (ref "C1") (pin "1") (pinfunction "1_1") (pintype "passive"))
      (node (ref "C21") (pin "1") (pinfunction "1_1") (pintype "passive"))
      (node (ref "C22") (pin "1") (pinfunction "1_1") (pintype "passive"))
      (node (ref "C26") (pin "1") (pinfunction "1_1") (pintype "passive"))
      (node (ref "C28") (pin "1") (pinfunction "1_1") (pintype "passive"))
      (node (ref "C31") (pin "1") (pinfunction "1_1") (pintype "passive"))
      (node (ref "C32") (pin "1") (pinfunction "1_1") (pintype "passive"))
      (node (ref "C38") (pin "2") (pinfunction "+_2") (pintype "passive"))
      (node (ref "C41") (pin "1") (pinfunction "1_1") (pintype "passive"))
      (node (ref "C57") (pin "2") (pinfunction "2_2") (pintype "passive"))
      (node (ref "C58") (pin "2") (pinfunction "2_2") (pintype "passive"))
      (node (ref "IC1") (pin "3") (pinfunction "P$3_3") (pintype "bidirectional"))
      (node (ref "IC10") (pin "4") (pinfunction "P$1_4") (pintype "bidirectional"))
      (node (ref "IC11") (pin "4") (pinfunction "P$1_4") (pintype "bidirectional"))
      (node (ref "IC5") (pin "P$2") (pinfunction "P$2_P$2") (pintype "bidirectional"))
      (node (ref "IC6") (pin "P$5") (pinfunction "P$5_P$5") (pintype "bidirectional"))
      (node (ref "IC6") (pin "P$6") (pinfunction "P$6_P$6") (pintype "bidirectional"))
      (node (ref "IC6") (pin "P$7") (pinfunction "P$7_P$7") (pintype "bidirectional"))
      (node (ref "IC8") (pin "3") (pinfunction "VO_3") (pintype "passive"))
      (node (ref "P1") (pin "P$4") (pinfunction "P$4_P$4") (pintype "bidirectional"))
      (node (ref "P3") (pin "LED") (pinfunction "P$8_LED") (pintype "bidirectional"))
      (node (ref "P3") (pin "LED1") (pinfunction "P$8_LED1") (pintype "bidirectional"))
      (node (ref "P3") (pin "RESET") (pinfunction "P$4_RESET") (pintype "bidirectional"))
      (node (ref "P3") (pin "RESET1") (pinfunction "P$4_RESET1") (pintype "bidirectional"))
      (node (ref "P3") (pin "VCC") (pinfunction "P$1_VCC") (pintype "bidirectional"))
      (node (ref "P3") (pin "VCC1") (pinfunction "P$1_VCC1") (pintype "bidirectional"))
      (node (ref "R18") (pin "2") (pinfunction "2_2") (pintype "passive"))
      (node (ref "R20") (pin "2") (pinfunction "2_2") (pintype "passive"))
      (node (ref "R22") (pin "2") (pinfunction "2_2") (pintype "passive"))
      (node (ref "R23") (pin "2") (pinfunction "2_2") (pintype "passive"))
      (node (ref "R24") (pin "1") (pinfunction "1_1") (pintype "passive"))
      (node (ref "R28") (pin "2") (pinfunction "2_2") (pintype "passive"))
      (node (ref "R29") (pin "2") (pinfunction "2_2") (pintype "passive"))
      (node (ref "R3") (pin "2") (pinfunction "2_2") (pintype "passive"))
      (node (ref "R31") (pin "2") (pinfunction "2_2") (pintype "passive"))
      (node (ref "R32") (pin "2") (pinfunction "2_2") (pintype "passive"))
      (node (ref "R36") (pin "1") (pinfunction "1_1") (pintype "passive"))
      (node (ref "R37") (pin "1") (pinfunction "1_1") (pintype "passive"))
    )
    (net (code "3") (name "+12V") (class "Default")
      (node (ref "C17") (pin "2") (pinfunction "2_2") (pintype "passive"))
      (node (ref "C19") (pin "2") (pinfunction "2_2") (pintype "passive"))
      (node (ref "C34") (pin "1") (pinfunction "1_1") (pintype "passive"))
      (node (ref "C39") (pin "2") (pinfunction "+_2") (pintype "passive"))
      (node (ref "F1") (pin "1") (pinfunction "P$1_1") (pintype "bidirectional"))
      (node (ref "IC2") (pin "8") (pinfunction "P$1_8") (pintype "bidirectional"))
      (node (ref "IC3") (pin "8") (pinfunction "P$1_8") (pintype "bidirectional"))
      (node (ref "IC7") (pin "1") (pinfunction "P$1_1") (pintype "bidirectional"))
      (node (ref "IC7") (pin "3") (pinfunction "P$3_3") (pintype "bidirectional"))
      (node (ref "R30") (pin "2") (pinfunction "2_2") (pintype "passive"))
    )
    (net (code "4") (name "-10V") (class "Default")
      (node (ref "C44") (pin "1") (pinfunction "1_1") (pintype "passive"))
      (node (ref "POT2") (pin "1") (pinfunction "A_1") (pintype "passive"))
      (node (ref "POT3") (pin "1") (pinfunction "A_1") (pintype "passive"))
      (node (ref "POT4") (pin "1") (pinfunction "A_1") (pintype "passive"))
      (node (ref "POT5") (pin "1") (pinfunction "A_1") (pintype "passive"))
      (node (ref "R33") (pin "1") (pinfunction "1_1") (pintype "passive"))
      (node (ref "R38") (pin "1") (pinfunction "1_1") (pintype "passive"))
      (node (ref "R40") (pin "1") (pinfunction "1_1") (pintype "passive"))
      (node (ref "R50") (pin "1") (pinfunction "1_1") (pintype "passive"))
      (node (ref "R52") (pin "1") (pinfunction "1_1") (pintype "passive"))
      (node (ref "U1") (pin "2") (pinfunction "A_2") (pintype "passive"))
    )
    (net (code "5") (name "-12V") (class "Default")
      (node (ref "C18") (pin "1") (pinfunction "1_1") (pintype "passive"))
      (node (ref "C20") (pin "1") (pinfunction "1_1") (pintype "passive"))
      (node (ref "C42") (pin "1") (pinfunction "-_1") (pintype "passive"))
      (node (ref "F2") (pin "1") (pinfunction "P$1_1") (pintype "bidirectional"))
      (node (ref "IC2") (pin "4") (pinfunction "P$2_4") (pintype "bidirectional"))
      (node (ref "IC3") (pin "4") (pinfunction "P$2_4") (pintype "bidirectional"))
      (node (ref "R33") (pin "2") (pinfunction "2_2") (pintype "passive"))
    )
    (net (code "6") (name "CVIN0") (class "Default")
      (node (ref "C49") (pin "2") (pinfunction "2_2") (pintype "passive"))
      (node (ref "IC10") (pin "1") (pinfunction "P$3_1") (pintype "bidirectional"))
      (node (ref "IC9") (pin "1") (pinfunction "P$1_1") (pintype "bidirectional"))
      (node (ref "R46") (pin "2") (pinfunction "2_2") (pintype "passive"))
    )
    (net (code "7") (name "CVIN1") (class "Default")
      (node (ref "C50") (pin "2") (pinfunction "2_2") (pintype "passive"))
      (node (ref "IC10") (pin "7") (pinfunction "P$3_7") (pintype "bidirectional"))
      (node (ref "IC9") (pin "2") (pinfunction "P$2_2") (pintype "bidirectional"))
      (node (ref "R47") (pin "2") (pinfunction "2_2") (pintype "passive"))
    )
    (net (code "8") (name "CVIN2") (class "Default")
      (node (ref "C53") (pin "2") (pinfunction "2_2") (pintype "passive"))
      (node (ref "IC10") (pin "8") (pinfunction "P$3_8") (pintype "bidirectional"))
      (node (ref "IC9") (pin "3") (pinfunction "P$3_3") (pintype "bidirectional"))
      (node (ref "R58") (pin "2") (pinfunction "2_2") (pintype "passive"))
    )
    (net (code "9") (name "CVIN3") (class "Default")
      (node (ref "C54") (pin "2") (pinfunction "2_2") (pintype "passive"))
      (node (ref "IC10") (pin "14") (pinfunction "P$3_14") (pintype "bidirectional"))
      (node (ref "IC9") (pin "4") (pinfunction "P$4_4") (pintype "bidirectional"))
      (node (ref "R59") (pin "2") (pinfunction "2_2") (pintype "passive"))
    )
    (net (code "10") (name "CVIN4") (class "Default")
      (node (ref "C51") (pin "2") (pinfunction "2_2") (pintype "passive"))
      (node (ref "IC11") (pin "1") (pinfunction "P$3_1") (pintype "bidirectional"))
      (node (ref "IC9") (pin "5") (pinfunction "P$5_5") (pintype "bidirectional"))
      (node (ref "R48") (pin "2") (pinfunction "2_2") (pintype "passive"))
    )
    (net (code "11") (name "CVIN5") (class "Default")
      (node (ref "C52") (pin "2") (pinfunction "2_2") (pintype "passive"))
      (node (ref "IC11") (pin "7") (pinfunction "P$3_7") (pintype "bidirectional"))
      (node (ref "IC9") (pin "6") (pinfunction "P$6_6") (pintype "bidirectional"))
      (node (ref "R49") (pin "2") (pinfunction "2_2") (pintype "passive"))
    )
    (net (code "12") (name "CVIN6") (class "Default")
      (node (ref "C55") (pin "2") (pinfunction "2_2") (pintype "passive"))
      (node (ref "IC11") (pin "14") (pinfunction "P$3_14") (pintype "bidirectional"))
      (node (ref "IC9") (pin "7") (pinfunction "P$7_7") (pintype "bidirectional"))
      (node (ref "R60") (pin "2") (pinfunction "2_2") (pintype "passive"))
    )
    (net (code "13") (name "CVIN7") (class "Default")
      (node (ref "C56") (pin "2") (pinfunction "2_2") (pintype "passive"))
      (node (ref "IC11") (pin "8") (pinfunction "P$3_8") (pintype "bidirectional"))
      (node (ref "IC9") (pin "8") (pinfunction "P$8_8") (pintype "bidirectional"))
      (node (ref "R61") (pin "2") (pinfunction "2_2") (pintype "passive"))
    )
    (net (code "14") (name "D+") (class "Default")
      (node (ref "IC6") (pin "P$3") (pinfunction "P$3_P$3") (pintype "bidirectional"))
      (node (ref "P2") (pin "P3") (pinfunction "P$3_P3") (pintype "bidirectional"))
    )
    (net (code "15") (name "D-") (class "Default")
      (node (ref "IC6") (pin "P$4") (pinfunction "P$4_P$4") (pintype "bidirectional"))
      (node (ref "P2") (pin "P2") (pinfunction "P$2_P2") (pintype "bidirectional"))
    )
    (net (code "16") (name "DTR") (class "Default")
      (node (ref "IC6") (pin "P$23") (pinfunction "P$23_P$23") (pintype "bidirectional"))
      (node (ref "Q3") (pin "2") (pinfunction "E_2") (pintype "passive"))
      (node (ref "Q4") (pin "2") (pinfunction "E_2") (pintype "passive"))
      (node (ref "R25") (pin "2") (pinfunction "2_2") (pintype "passive"))
    )
    (net (code "17") (name "EN") (class "Default")
      (node (ref "C6") (pin "1") (pinfunction "1_1") (pintype "passive"))
      (node (ref "IC1") (pin "2") (pinfunction "P$2_2") (pintype "bidirectional"))
      (node (ref "IC5") (pin "P$3") (pinfunction "P$3_P$3") (pintype "bidirectional"))
      (node (ref "Q2") (pin "3") (pinfunction "C_3") (pintype "passive"))
      (node (ref "R3") (pin "1") (pinfunction "1_1") (pintype "passive"))
    )
    (net (code "18") (name "GND") (class "Default")
      (node (ref "C1") (pin "2") (pinfunction "2_2") (pintype "passive"))
      (node (ref "C10") (pin "1") (pinfunction "1_1") (pintype "passive"))
      (node (ref "C11") (pin "2") (pinfunction "2_2") (pintype "passive"))
      (node (ref "C14") (pin "2") (pinfunction "2_2") (pintype "passive"))
      (node (ref "C15") (pin "2") (pinfunction "2_2") (pintype "passive"))
      (node (ref "C16") (pin "2") (pinfunction "2_2") (pintype "passive"))
      (node (ref "C17") (pin "1") (pinfunction "1_1") (pintype "passive"))
      (node (ref "C18") (pin "2") (pinfunction "2_2") (pintype "passive"))
      (node (ref "C19") (pin "1") (pinfunction "1_1") (pintype "passive"))
      (node (ref "C20") (pin "2") (pinfunction "2_2") (pintype "passive"))
      (node (ref "C21") (pin "2") (pinfunction "2_2") (pintype "passive"))
      (node (ref "C22") (pin "2") (pinfunction "2_2") (pintype "passive"))
      (node (ref "C23") (pin "1") (pinfunction "1_1") (pintype "passive"))
      (node (ref "C24") (pin "1") (pinfunction "1_1") (pintype "passive"))
      (node (ref "C25") (pin "1") (pinfunction "1_1") (pintype "passive"))
      (node (ref "C26") (pin "2") (pinfunction "2_2") (pintype "passive"))
      (node (ref "C27") (pin "1") (pinfunction "1_1") (pintype "passive"))
      (node (ref "C28") (pin "2") (pinfunction "2_2") (pintype "passive"))
      (node (ref "C29") (pin "1") (pinfunction "1_1") (pintype "passive"))
      (node (ref "C30") (pin "1") (pinfunction "1_1") (pintype "passive"))
      (node (ref "C31") (pin "2") (pinfunction "2_2") (pintype "passive"))
      (node (ref "C32") (pin "2") (pinfunction "2_2") (pintype "passive"))
      (node (ref "C33") (pin "2") (pinfunction "2_2") (pintype "passive"))
      (node (ref "C34") (pin "2") (pinfunction "2_2") (pintype "passive"))
      (node (ref "C35") (pin "2") (pinfunction "2_2") (pintype "passive"))
      (node (ref "C36") (pin "-") (pinfunction "-_-") (pintype "passive"))
      (node (ref "C37") (pin "2") (pinfunction "2_2") (pintype "passive"))
      (node (ref "C38") (pin "1") (pinfunction "-_1") (pintype "passive"))
      (node (ref "C39") (pin "1") (pinfunction "-_1") (pintype "passive"))
      (node (ref "C4") (pin "1") (pinfunction "1_1") (pintype "passive"))
      (node (ref "C40") (pin "2") (pinfunction "2_2") (pintype "passive"))
      (node (ref "C41") (pin "2") (pinfunction "2_2") (pintype "passive"))
      (node (ref "C42") (pin "2") (pinfunction "+_2") (pintype "passive"))
      (node (ref "C43") (pin "1") (pinfunction "1_1") (pintype "passive"))
      (node (ref "C44") (pin "2") (pinfunction "2_2") (pintype "passive"))
      (node (ref "C45") (pin "1") (pinfunction "1_1") (pintype "passive"))
      (node (ref "C46") (pin "1") (pinfunction "1_1") (pintype "passive"))
      (node (ref "C47") (pin "2") (pinfunction "2_2") (pintype "passive"))
      (node (ref "C48") (pin "2") (pinfunction "2_2") (pintype "passive"))
      (node (ref "C5") (pin "1") (pinfunction "1_1") (pintype "passive"))
      (node (ref "C57") (pin "1") (pinfunction "1_1") (pintype "passive"))
      (node (ref "C58") (pin "1") (pinfunction "1_1") (pintype "passive"))
      (node (ref "C6") (pin "2") (pinfunction "2_2") (pintype "passive"))
      (node (ref "C9") (pin "1") (pinfunction "1_1") (pintype "passive"))
      (node (ref "IC1") (pin "1") (pinfunction "P$1_1") (pintype "bidirectional"))
      (node (ref "IC10") (pin "10") (pinfunction "P$1_10") (pintype "bidirectional"))
      (node (ref "IC10") (pin "11") (pinfunction "P$2_11") (pintype "bidirectional"))
      (node (ref "IC10") (pin "12") (pinfunction "P$1_12") (pintype "bidirectional"))
      (node (ref "IC10") (pin "3") (pinfunction "P$1_3") (pintype "bidirectional"))
      (node (ref "IC10") (pin "5") (pinfunction "P$1_5") (pintype "bidirectional"))
      (node (ref "IC11") (pin "10") (pinfunction "P$1_10") (pintype "bidirectional"))
      (node (ref "IC11") (pin "11") (pinfunction "P$2_11") (pintype "bidirectional"))
      (node (ref "IC11") (pin "12") (pinfunction "P$1_12") (pintype "bidirectional"))
      (node (ref "IC11") (pin "3") (pinfunction "P$1_3") (pintype "bidirectional"))
      (node (ref "IC11") (pin "5") (pinfunction "P$1_5") (pintype "bidirectional"))
      (node (ref "IC2") (pin "3") (pinfunction "P$1_3") (pintype "bidirectional"))
      (node (ref "IC2") (pin "5") (pinfunction "P$1_5") (pintype "bidirectional"))
      (node (ref "IC3") (pin "3") (pinfunction "P$1_3") (pintype "bidirectional"))
      (node (ref "IC3") (pin "5") (pinfunction "P$1_5") (pintype "bidirectional"))
      (node (ref "IC4") (pin "11") (pinfunction "HPGND_11") (pintype "bidirectional"))
      (node (ref "IC4") (pin "15") (pinfunction "AGND_15") (pintype "bidirectional"))
      (node (ref "IC4") (pin "28") (pinfunction "DGND_28") (pintype "bidirectional"))
      (node (ref "IC5") (pin "GND") (pinfunction "P$1_GND") (pintype "bidirectional"))
      (node (ref "IC5") (pin "GND2") (pinfunction "P$1_GND2") (pintype "bidirectional"))
      (node (ref "IC5") (pin "P$1") (pinfunction "P$1_P$1") (pintype "bidirectional"))
      (node (ref "IC5") (pin "P$15") (pinfunction "P$15_P$15") (pintype "bidirectional"))
      (node (ref "IC5") (pin "P$38") (pinfunction "P$38_P$38") (pintype "bidirectional"))
      (node (ref "IC6") (pin "GND") (pinfunction "P$2_GND") (pintype "bidirectional"))
      (node (ref "IC6") (pin "GND2") (pinfunction "P$2_GND2") (pintype "bidirectional"))
      (node (ref "IC6") (pin "P$2") (pinfunction "P$2_P$2") (pintype "bidirectional"))
      (node (ref "IC7") (pin "2") (pinfunction "P$2_2") (pintype "bidirectional"))
      (node (ref "IC8") (pin "2") (pinfunction "GND_2") (pintype "passive"))
      (node (ref "IC9") (pin "14") (pinfunction "P$14_14") (pintype "bidirectional"))
      (node (ref "IC9") (pin "9") (pinfunction "P$9_9") (pintype "bidirectional"))
      (node (ref "J1") (pin "GND") (pinfunction "GND_GND") (pintype "passive"))
      (node (ref "J1") (pin "NORM") (pinfunction "NORM_NORM") (pintype "passive"))
      (node (ref "J10") (pin "GND") (pinfunction "GND_GND") (pintype "passive"))
      (node (ref "J10") (pin "NORM") (pinfunction "NORM_NORM") (pintype "passive"))
      (node (ref "J11") (pin "GND") (pinfunction "GND_GND") (pintype "passive"))
      (node (ref "J11") (pin "NORM") (pinfunction "NORM_NORM") (pintype "passive"))
      (node (ref "J12") (pin "GND") (pinfunction "GND_GND") (pintype "passive"))
      (node (ref "J12") (pin "NORM") (pinfunction "NORM_NORM") (pintype "passive"))
      (node (ref "J13") (pin "GND") (pinfunction "GND_GND") (pintype "passive"))
      (node (ref "J13") (pin "NORM") (pinfunction "NORM_NORM") (pintype "passive"))
      (node (ref "J14") (pin "GND") (pinfunction "GND_GND") (pintype "passive"))
      (node (ref "J14") (pin "NORM") (pinfunction "NORM_NORM") (pintype "passive"))
      (node (ref "J2") (pin "GND") (pinfunction "GND_GND") (pintype "passive"))
      (node (ref "J2") (pin "NORM") (pinfunction "NORM_NORM") (pintype "passive"))
      (node (ref "J3") (pin "GND") (pinfunction "GND_GND") (pintype "passive"))
      (node (ref "J4") (pin "GND") (pinfunction "GND_GND") (pintype "passive"))
      (node (ref "J5") (pin "GND") (pinfunction "GND_GND") (pintype "passive"))
      (node (ref "J5") (pin "NORM") (pinfunction "NORM_NORM") (pintype "passive"))
      (node (ref "J6") (pin "GND") (pinfunction "GND_GND") (pintype "passive"))
      (node (ref "J6") (pin "NORM") (pinfunction "NORM_NORM") (pintype "passive"))
      (node (ref "J7") (pin "GND") (pinfunction "GND_GND") (pintype "passive"))
      (node (ref "J7") (pin "NORM") (pinfunction "NORM_NORM") (pintype "passive"))
      (node (ref "J8") (pin "GND") (pinfunction "GND_GND") (pintype "passive"))
      (node (ref "J8") (pin "NORM") (pinfunction "NORM_NORM") (pintype "passive"))
      (node (ref "J9") (pin "GND") (pinfunction "GND_GND") (pintype "passive"))
      (node (ref "J9") (pin "NORM") (pinfunction "NORM_NORM") (pintype "passive"))
      (node (ref "L1") (pin "K") (pinfunction "C_K") (pintype "passive"))
      (node (ref "P1") (pin "P$10") (pinfunction "P$9_P$10") (pintype "bidirectional"))
      (node (ref "P1") (pin "P$6") (pinfunction "P$6_P$6") (pintype "bidirectional"))
      (node (ref "P1") (pin "P$9") (pinfunction "P$9_P$9") (pintype "bidirectional"))
      (node (ref "P2") (pin "P$1") (pinfunction "P$6_P$1") (pintype "bidirectional"))
      (node (ref "P2") (pin "P$10") (pinfunction "P$6_P$10") (pintype "bidirectional"))
      (node (ref "P2") (pin "P$11") (pinfunction "P$6_P$11") (pintype "bidirectional"))
      (node (ref "P2") (pin "P$2") (pinfunction "P$6_P$2") (pintype "bidirectional"))
      (node (ref "P2") (pin "P$8") (pinfunction "P$6_P$8") (pintype "bidirectional"))
      (node (ref "P2") (pin "P$9") (pinfunction "P$6_P$9") (pintype "bidirectional"))
      (node (ref "P2") (pin "P5") (pinfunction "P$5_P5") (pintype "bidirectional"))
      (node (ref "P3") (pin "GND") (pinfunction "P$2_GND") (pintype "bidirectional"))
      (node (ref "P3") (pin "GND1") (pinfunction "P$2_GND1") (pintype "bidirectional"))
      (node (ref "P4") (pin "3") (pinfunction "GND_3") (pintype "bidirectional"))
      (node (ref "P4") (pin "4") (pinfunction "GND_4") (pintype "bidirectional"))
      (node (ref "P4") (pin "5") (pinfunction "GND_5") (pintype "bidirectional"))
      (node (ref "P4") (pin "6") (pinfunction "GND_6") (pintype "bidirectional"))
      (node (ref "P4") (pin "7") (pinfunction "GND_7") (pintype "bidirectional"))
      (node (ref "P4") (pin "8") (pinfunction "GND_8") (pintype "bidirectional"))
      (node (ref "POT2") (pin "3") (pinfunction "B_3") (pintype "passive"))
      (node (ref "POT3") (pin "3") (pinfunction "B_3") (pintype "passive"))
      (node (ref "POT4") (pin "3") (pinfunction "B_3") (pintype "passive"))
      (node (ref "POT5") (pin "3") (pinfunction "B_3") (pintype "passive"))
      (node (ref "Q5") (pin "2") (pinfunction "E_2") (pintype "passive"))
      (node (ref "Q6") (pin "2") (pinfunction "E_2") (pintype "passive"))
      (node (ref "R1") (pin "2") (pinfunction "2_2") (pintype "passive"))
      (node (ref "R16") (pin "2") (pinfunction "2_2") (pintype "passive"))
      (node (ref "R17") (pin "2") (pinfunction "2_2") (pintype "passive"))
      (node (ref "R2") (pin "2") (pinfunction "2_2") (pintype "passive"))
      (node (ref "R21") (pin "1") (pinfunction "1_1") (pintype "passive"))
      (node (ref "SW1") (pin "C") (pinfunction "C_C") (pintype "passive"))
      (node (ref "SW1") (pin "D") (pinfunction "1_D") (pintype "passive"))
      (node (ref "SW2") (pin "P$3") (pinfunction "3_P$3") (pintype "passive"))
      (node (ref "SW2") (pin "P$4") (pinfunction "4_P$4") (pintype "passive"))
      (node (ref "SW3") (pin "P$3") (pinfunction "3_P$3") (pintype "passive"))
      (node (ref "SW3") (pin "P$4") (pinfunction "4_P$4") (pintype "passive"))
      (node (ref "U1") (pin "1") (pinfunction "C_1") (pintype "passive"))
    )
    (net (code "19") (name "IO0") (class "Default")
      (node (ref "IC5") (pin "P$25") (pinfunction "P$25_P$25") (pintype "bidirectional"))
      (node (ref "IC9") (pin "12") (pinfunction "P$12_12") (pintype "bidirectional"))
      (node (ref "Q3") (pin "3") (pinfunction "C_3") (pintype "passive"))
    )
    (net (code "20") (name "IO2") (class "Default")
      (node (ref "IC5") (pin "P$24") (pinfunction "P$24_P$24") (pintype "bidirectional"))
      (node (ref "P1") (pin "P$7") (pinfunction "P$7_P$7") (pintype "bidirectional"))
      (node (ref "Q4") (pin "3") (pinfunction "C_3") (pintype "passive"))
      (node (ref "R23") (pin "1") (pinfunction "1_1") (pintype "passive"))
    )
    (net (code "21") (name "IO4") (class "Default")
      (node (ref "IC4") (pin "22") (pinfunction "CSB_22") (pintype "bidirectional"))
      (node (ref "IC5") (pin "P$26") (pinfunction "P$26_P$26") (pintype "bidirectional"))
    )
    (net (code "22") (name "IO5") (class "Default")
      (node (ref "IC5") (pin "P$29") (pinfunction "P$29_P$29") (pintype "bidirectional"))
      (node (ref "P3") (pin "CS") (pinfunction "P$3_CS") (pintype "bidirectional"))
      (node (ref "P3") (pin "CS1") (pinfunction "P$3_CS1") (pintype "bidirectional"))
    )
    (net (code "23") (name "IO12") (class "Default")
      (node (ref "IC4") (pin "24") (pinfunction "SCLK_24") (pintype "bidirectional"))
      (node (ref "IC5") (pin "P$14") (pinfunction "P$14_P$14") (pintype "bidirectional"))
      (node (ref "IC9") (pin "13") (pinfunction "P$13_13") (pintype "bidirectional"))
    )
    (net (code "24") (name "IO13") (class "Default")
      (node (ref "IC4") (pin "23") (pinfunction "SDIN_23") (pintype "bidirectional"))
      (node (ref "IC5") (pin "P$16") (pinfunction "P$16_P$16") (pintype "bidirectional"))
      (node (ref "IC9") (pin "11") (pinfunction "P$11_11") (pintype "bidirectional"))
    )
    (net (code "25") (name "IO14") (class "Default")
      (node (ref "IC5") (pin "P$13") (pinfunction "P$13_P$13") (pintype "bidirectional"))
      (node (ref "P1") (pin "P$5") (pinfunction "P$5_P$5") (pintype "bidirectional"))
      (node (ref "R22") (pin "1") (pinfunction "1_1") (pintype "passive"))
    )
    (net (code "26") (name "IO15") (class "Default")
      (node (ref "IC5") (pin "P$23") (pinfunction "P$23_P$23") (pintype "bidirectional"))
      (node (ref "P1") (pin "P$3") (pinfunction "P$3_P$3") (pintype "bidirectional"))
      (node (ref "R20") (pin "1") (pinfunction "1_1") (pintype "passive"))
    )
    (net (code "27") (name "IO18") (class "Default")
      (node (ref "IC5") (pin "P$30") (pinfunction "P$30_P$30") (pintype "bidirectional"))
      (node (ref "P3") (pin "SCK") (pinfunction "P$7_SCK") (pintype "bidirectional"))
      (node (ref "P3") (pin "SCK1") (pinfunction "P$7_SCK1") (pintype "bidirectional"))
    )
    (net (code "28") (name "IO19") (class "Default")
      (node (ref "IC5") (pin "P$31") (pinfunction "P$31_P$31") (pintype "bidirectional"))
      (node (ref "SJ1") (pin "2") (pinfunction "2_2") (pintype "passive"))
    )
    (net (code "29") (name "IO21") (class "Default")
      (node (ref "IC4") (pin "3") (pinfunction "BCLK_3") (pintype "bidirectional"))
      (node (ref "IC5") (pin "P$33") (pinfunction "P$33_P$33") (pintype "bidirectional"))
    )
    (net (code "30") (name "IO22") (class "Default")
      (node (ref "IC4") (pin "4") (pinfunction "DACDAT_4") (pintype "bidirectional"))
      (node (ref "IC5") (pin "P$36") (pinfunction "P$36_P$36") (pintype "bidirectional"))
    )
    (net (code "31") (name "IO23") (class "Default")
      (node (ref "IC5") (pin "P$37") (pinfunction "P$37_P$37") (pintype "bidirectional"))
      (node (ref "P3") (pin "SDI/MOSI") (pinfunction "P$6_SDI/MOSI") (pintype "bidirectional"))
      (node (ref "P3") (pin "SDI/MOSI1") (pinfunction "P$6_SDI/MOSI1") (pintype "bidirectional"))
    )
    (net (code "32") (name "IO25") (class "Default")
      (node (ref "IC4") (pin "5") (pinfunction "DACLRC_5") (pintype "bidirectional"))
      (node (ref "IC4") (pin "7") (pinfunction "ADCLRC_7") (pintype "bidirectional"))
      (node (ref "IC5") (pin "P$10") (pinfunction "P$10_P$10") (pintype "bidirectional"))
    )
    (net (code "33") (name "IO26") (class "Default")
      (node (ref "IC5") (pin "P$11") (pinfunction "P$11_P$11") (pintype "bidirectional"))
      (node (ref "P3") (pin "DC/RS") (pinfunction "P$5_DC/RS") (pintype "bidirectional"))
      (node (ref "P3") (pin "DC/RS1") (pinfunction "P$5_DC/RS1") (pintype "bidirectional"))
    )
    (net (code "34") (name "IO27") (class "Default")
      (node (ref "IC4") (pin "6") (pinfunction "ADCDAT_6") (pintype "bidirectional"))
      (node (ref "IC5") (pin "P$12") (pinfunction "P$12_P$12") (pintype "bidirectional"))
    )
    (net (code "35") (name "IO32") (class "Default")
      (node (ref "IC5") (pin "P$8") (pinfunction "P$8_P$8") (pintype "bidirectional"))
      (node (ref "IC9") (pin "10") (pinfunction "P$10_10") (pintype "bidirectional"))
    )
    (net (code "36") (name "IO33") (class "Default")
      (node (ref "C35") (pin "1") (pinfunction "1_1") (pintype "passive"))
      (node (ref "IC5") (pin "P$9") (pinfunction "P$9_P$9") (pintype "bidirectional"))
      (node (ref "R29") (pin "1") (pinfunction "1_1") (pintype "passive"))
      (node (ref "SW1") (pin "B") (pinfunction "B_B") (pintype "passive"))
    )
    (net (code "37") (name "IO34") (class "Default")
      (node (ref "C37") (pin "1") (pinfunction "1_1") (pintype "passive"))
      (node (ref "IC5") (pin "P$6") (pinfunction "P$6_P$6") (pintype "bidirectional"))
      (node (ref "R31") (pin "1") (pinfunction "1_1") (pintype "passive"))
      (node (ref "SW1") (pin "E") (pinfunction "2_E") (pintype "passive"))
    )
    (net (code "38") (name "IO35") (class "Default")
      (node (ref "C33") (pin "1") (pinfunction "1_1") (pintype "passive"))
      (node (ref "IC5") (pin "P$7") (pinfunction "P$7_P$7") (pintype "bidirectional"))
      (node (ref "R28") (pin "1") (pinfunction "1_1") (pintype "passive"))
      (node (ref "SW1") (pin "A") (pinfunction "A_A") (pintype "passive"))
    )
    (net (code "39") (name "LHPOUT") (class "Default")
      (node (ref "IC4") (pin "9") (pinfunction "LHPOUT_9") (pintype "bidirectional"))
    )
    (net (code "40") (name "LIN") (class "Default")
      (node (ref "C13") (pin "1") (pinfunction "1_1") (pintype "passive"))
      (node (ref "IC4") (pin "20") (pinfunction "LLINEIN_20") (pintype "bidirectional"))
    )
    (net (code "41") (name "LOUT") (class "Default")
      (node (ref "C3") (pin "2") (pinfunction "2_2") (pintype "passive"))
      (node (ref "IC4") (pin "12") (pinfunction "LOUT_12") (pintype "bidirectional"))
    )
    (net (code "42") (name "MICBIAS") (class "Default")
      (node (ref "IC4") (pin "17") (pinfunction "MICBIAS_17") (pintype "bidirectional"))
    )
    (net (code "43") (name "MICIN") (class "Default")
      (node (ref "IC4") (pin "18") (pinfunction "MICIN_18") (pintype "bidirectional"))
    )
    (net (code "44") (name "Net-(C2-Pad1)") (class "Default")
      (node (ref "C2") (pin "1") (pinfunction "1_1") (pintype "passive"))
      (node (ref "R1") (pin "1") (pinfunction "1_1") (pintype "passive"))
      (node (ref "R6") (pin "1") (pinfunction "1_1") (pintype "passive"))
    )
    (net (code "45") (name "Net-(C3-Pad1)") (class "Default")
      (node (ref "C3") (pin "1") (pinfunction "1_1") (pintype "passive"))
      (node (ref "R2") (pin "1") (pinfunction "1_1") (pintype "passive"))
      (node (ref "R7") (pin "1") (pinfunction "1_1") (pintype "passive"))
    )
    (net (code "46") (name "Net-(C10-Pad2)") (class "Default")
      (node (ref "C10") (pin "2") (pinfunction "2_2") (pintype "passive"))
      (node (ref "C13") (pin "2") (pinfunction "2_2") (pintype "passive"))
      (node (ref "R15") (pin "1") (pinfunction "1_1") (pintype "passive"))
      (node (ref "R17") (pin "1") (pinfunction "1_1") (pintype "passive"))
    )
    (net (code "47") (name "Net-(C12-Pad2)") (class "Default")
      (node (ref "C12") (pin "2") (pinfunction "2_2") (pintype "passive"))
      (node (ref "C9") (pin "2") (pinfunction "2_2") (pintype "passive"))
      (node (ref "R14") (pin "1") (pinfunction "1_1") (pintype "passive"))
      (node (ref "R16") (pin "1") (pinfunction "1_1") (pintype "passive"))
    )
    (net (code "48") (name "Net-(D1-Pad+)") (class "Default")
      (node (ref "D1") (pin "+") (pinfunction "+_+") (pintype "passive"))
      (node (ref "P4") (pin "10") (pinfunction "+12V_10") (pintype "bidirectional"))
      (node (ref "P4") (pin "9") (pinfunction "+12V_9") (pintype "bidirectional"))
    )
    (net (code "49") (name "Net-(D2-Pad-)") (class "Default")
      (node (ref "D2") (pin "-") (pinfunction "-_-") (pintype "passive"))
      (node (ref "P4") (pin "1") (pinfunction "-12V_1") (pintype "bidirectional"))
      (node (ref "P4") (pin "2") (pinfunction "-12V_2") (pintype "bidirectional"))
    )
    (net (code "50") (name "Net-(F1-P$2)") (class "Default")
      (node (ref "D1") (pin "-") (pinfunction "-_-") (pintype "passive"))
      (node (ref "F1") (pin "2") (pinfunction "P$2_2") (pintype "bidirectional"))
    )
    (net (code "51") (name "Net-(F2-P$2)") (class "Default")
      (node (ref "D2") (pin "+") (pinfunction "+_+") (pintype "passive"))
      (node (ref "F2") (pin "2") (pinfunction "P$2_2") (pintype "bidirectional"))
    )
    (net (code "52") (name "Net-(IC2A-P$2)") (class "Default")
      (node (ref "IC2") (pin "2") (pinfunction "P$2_2") (pintype "bidirectional"))
      (node (ref "R4") (pin "1") (pinfunction "1_1") (pintype "passive"))
      (node (ref "R8") (pin "2") (pinfunction "2_2") (pintype "passive"))
    )
    (net (code "53") (name "Net-(IC2A-P$3)") (class "Default")
      (node (ref "IC2") (pin "1") (pinfunction "P$3_1") (pintype "bidirectional"))
      (node (ref "POT1") (pin "R1_2") (pinfunction "W_R1_2") (pintype "passive"))
      (node (ref "POT1") (pin "R1_3") (pinfunction "B_R1_3") (pintype "passive"))
      (node (ref "R14") (pin "2") (pinfunction "2_2") (pintype "passive"))
    )
    (net (code "54") (name "Net-(IC2B-P$2)") (class "Default")
      (node (ref "IC2") (pin "6") (pinfunction "P$2_6") (pintype "bidirectional"))
      (node (ref "R5") (pin "1") (pinfunction "1_1") (pintype "passive"))
      (node (ref "R9") (pin "2") (pinfunction "2_2") (pintype "passive"))
    )
    (net (code "55") (name "Net-(IC2B-P$3)") (class "Default")
      (node (ref "IC2") (pin "7") (pinfunction "P$3_7") (pintype "bidirectional"))
      (node (ref "POT1") (pin "R2_2") (pinfunction "W_R2_2") (pintype "passive"))
      (node (ref "POT1") (pin "R2_3") (pinfunction "B_R2_3") (pintype "passive"))
      (node (ref "R15") (pin "2") (pinfunction "2_2") (pintype "passive"))
    )
    (net (code "56") (name "Net-(IC3A-P$2)") (class "Default")
      (node (ref "C7") (pin "2") (pinfunction "2_2") (pintype "passive"))
      (node (ref "IC3") (pin "2") (pinfunction "P$2_2") (pintype "bidirectional"))
      (node (ref "R10") (pin "1") (pinfunction "1_1") (pintype "passive"))
      (node (ref "R6") (pin "2") (pinfunction "2_2") (pintype "passive"))
    )
    (net (code "57") (name "Net-(IC3A-P$3)") (class "Default")
      (node (ref "C7") (pin "1") (pinfunction "1_1") (pintype "passive"))
      (node (ref "IC3") (pin "1") (pinfunction "P$3_1") (pintype "bidirectional"))
      (node (ref "R10") (pin "2") (pinfunction "2_2") (pintype "passive"))
      (node (ref "R12") (pin "1") (pinfunction "1_1") (pintype "passive"))
    )
    (net (code "58") (name "Net-(IC3B-P$2)") (class "Default")
      (node (ref "C8") (pin "2") (pinfunction "2_2") (pintype "passive"))
      (node (ref "IC3") (pin "6") (pinfunction "P$2_6") (pintype "bidirectional"))
      (node (ref "R11") (pin "1") (pinfunction "1_1") (pintype "passive"))
      (node (ref "R7") (pin "2") (pinfunction "2_2") (pintype "passive"))
    )
    (net (code "59") (name "Net-(IC3B-P$3)") (class "Default")
      (node (ref "C8") (pin "1") (pinfunction "1_1") (pintype "passive"))
      (node (ref "IC3") (pin "7") (pinfunction "P$3_7") (pintype "bidirectional"))
      (node (ref "R11") (pin "2") (pinfunction "2_2") (pintype "passive"))
      (node (ref "R13") (pin "1") (pinfunction "1_1") (pintype "passive"))
    )
    (net (code "60") (name "Net-(IC4-VMID)") (class "Default")
      (node (ref "C11") (pin "1") (pinfunction "1_1") (pintype "passive"))
      (node (ref "C14") (pin "1") (pinfunction "1_1") (pintype "passive"))
      (node (ref "IC4") (pin "16") (pinfunction "VMID_16") (pintype "bidirectional"))
    )
    (net (code "61") (name "Net-(IC4-XTI{slash}MCLK)") (class "Default")
      (node (ref "C4") (pin "2") (pinfunction "2_2") (pintype "passive"))
      (node (ref "IC4") (pin "25") (pinfunction "XTI/MCLK_25") (pintype "bidirectional"))
      (node (ref "Q1") (pin "1") (pinfunction "1_1") (pintype "passive"))
    )
    (net (code "62") (name "Net-(IC4-XTO)") (class "Default")
      (node (ref "C5") (pin "2") (pinfunction "2_2") (pintype "passive"))
      (node (ref "IC4") (pin "26") (pinfunction "XTO_26") (pintype "bidirectional"))
      (node (ref "Q1") (pin "2") (pinfunction "2_2") (pintype "passive"))
    )
    (net (code "63") (name "Net-(IC6-PadP$8)") (class "Default")
      (node (ref "IC6") (pin "P$8") (pinfunction "P$8_P$8") (pintype "bidirectional"))
      (node (ref "R19") (pin "1") (pinfunction "1_1") (pintype "passive"))
      (node (ref "R21") (pin "2") (pinfunction "2_2") (pintype "passive"))
    )
    (net (code "64") (name "Net-(IC6-PadP$9)") (class "Default")
      (node (ref "IC6") (pin "P$9") (pinfunction "P$9_P$9") (pintype "bidirectional"))
      (node (ref "R24") (pin "2") (pinfunction "2_2") (pintype "passive"))
    )
    (net (code "65") (name "Net-(IC8-VI)") (class "Default")
      (node (ref "C36") (pin "+") (pinfunction "+_+") (pintype "passive"))
      (node (ref "IC8") (pin "1") (pinfunction "VI_1") (pintype "input"))
      (node (ref "R30") (pin "1") (pinfunction "1_1") (pintype "passive"))
    )
    (net (code "66") (name "Net-(IC10A-P$2)") (class "Default")
      (node (ref "C49") (pin "1") (pinfunction "1_1") (pintype "passive"))
      (node (ref "IC10") (pin "2") (pinfunction "P$2_2") (pintype "bidirectional"))
      (node (ref "R38") (pin "2") (pinfunction "2_2") (pintype "passive"))
      (node (ref "R39") (pin "2") (pinfunction "2_2") (pintype "passive"))
      (node (ref "R46") (pin "1") (pinfunction "1_1") (pintype "passive"))
    )
    (net (code "67") (name "Net-(IC10B-P$2)") (class "Default")
      (node (ref "C50") (pin "1") (pinfunction "1_1") (pintype "passive"))
      (node (ref "IC10") (pin "6") (pinfunction "P$2_6") (pintype "bidirectional"))
      (node (ref "R40") (pin "2") (pinfunction "2_2") (pintype "passive"))
      (node (ref "R41") (pin "2") (pinfunction "2_2") (pintype "passive"))
      (node (ref "R47") (pin "1") (pinfunction "1_1") (pintype "passive"))
    )
    (net (code "68") (name "Net-(IC10C-P$2)") (class "Default")
      (node (ref "C53") (pin "1") (pinfunction "1_1") (pintype "passive"))
      (node (ref "IC10") (pin "9") (pinfunction "P$2_9") (pintype "bidirectional"))
      (node (ref "R50") (pin "2") (pinfunction "2_2") (pintype "passive"))
      (node (ref "R51") (pin "2") (pinfunction "2_2") (pintype "passive"))
      (node (ref "R58") (pin "1") (pinfunction "1_1") (pintype "passive"))
    )
    (net (code "69") (name "Net-(IC10D-P$2)") (class "Default")
      (node (ref "C54") (pin "1") (pinfunction "1_1") (pintype "passive"))
      (node (ref "IC10") (pin "13") (pinfunction "P$2_13") (pintype "bidirectional"))
      (node (ref "R52") (pin "2") (pinfunction "2_2") (pintype "passive"))
      (node (ref "R53") (pin "2") (pinfunction "2_2") (pintype "passive"))
      (node (ref "R59") (pin "1") (pinfunction "1_1") (pintype "passive"))
    )
    (net (code "70") (name "Net-(IC11A-P$2)") (class "Default")
      (node (ref "C51") (pin "1") (pinfunction "1_1") (pintype "passive"))
      (node (ref "IC11") (pin "2") (pinfunction "P$2_2") (pintype "bidirectional"))
      (node (ref "R42") (pin "2") (pinfunction "2_2") (pintype "passive"))
      (node (ref "R43") (pin "2") (pinfunction "2_2") (pintype "passive"))
      (node (ref "R48") (pin "1") (pinfunction "1_1") (pintype "passive"))
    )
    (net (code "71") (name "Net-(IC11B-P$2)") (class "Default")
      (node (ref "C52") (pin "1") (pinfunction "1_1") (pintype "passive"))
      (node (ref "IC11") (pin "6") (pinfunction "P$2_6") (pintype "bidirectional"))
      (node (ref "R44") (pin "2") (pinfunction "2_2") (pintype "passive"))
      (node (ref "R45") (pin "2") (pinfunction "2_2") (pintype "passive"))
      (node (ref "R49") (pin "1") (pinfunction "1_1") (pintype "passive"))
    )
    (net (code "72") (name "Net-(IC11C-P$2)") (class "Default")
      (node (ref "C56") (pin "1") (pinfunction "1_1") (pintype "passive"))
      (node (ref "IC11") (pin "9") (pinfunction "P$2_9") (pintype "bidirectional"))
      (node (ref "R56") (pin "2") (pinfunction "2_2") (pintype "passive"))
      (node (ref "R57") (pin "2") (pinfunction "2_2") (pintype "passive"))
      (node (ref "R61") (pin "1") (pinfunction "1_1") (pintype "passive"))
    )
    (net (code "73") (name "Net-(IC11D-P$2)") (class "Default")
      (node (ref "C55") (pin "1") (pinfunction "1_1") (pintype "passive"))
      (node (ref "IC11") (pin "13") (pinfunction "P$2_13") (pintype "bidirectional"))
      (node (ref "R54") (pin "2") (pinfunction "2_2") (pintype "passive"))
      (node (ref "R55") (pin "2") (pinfunction "2_2") (pintype "passive"))
      (node (ref "R60") (pin "1") (pinfunction "1_1") (pintype "passive"))
    )
    (net (code "74") (name "Net-(J1-PadIN)") (class "Default")
      (node (ref "J1") (pin "IN") (pinfunction "IN_IN") (pintype "passive"))
      (node (ref "R4") (pin "2") (pinfunction "2_2") (pintype "passive"))
    )
    (net (code "75") (name "Net-(J2-PadIN)") (class "Default")
      (node (ref "J2") (pin "IN") (pinfunction "IN_IN") (pintype "passive"))
      (node (ref "R5") (pin "2") (pinfunction "2_2") (pintype "passive"))
    )
    (net (code "76") (name "Net-(J3-PadIN)") (class "Default")
      (node (ref "J3") (pin "IN") (pinfunction "IN_IN") (pintype "passive"))
      (node (ref "R12") (pin "2") (pinfunction "2_2") (pintype "passive"))
    )
    (net (code "77") (name "Net-(J4-PadIN)") (class "Default")
      (node (ref "J4") (pin "IN") (pinfunction "IN_IN") (pintype "passive"))
      (node (ref "R13") (pin "2") (pinfunction "2_2") (pintype "passive"))
    )
    (net (code "78") (name "Net-(J5-PadIN)") (class "Default")
      (node (ref "J5") (pin "IN") (pinfunction "IN_IN") (pintype "passive"))
      (node (ref "R34") (pin "2") (pinfunction "2_2") (pintype "passive"))
    )
    (net (code "79") (name "Net-(J6-PadIN)") (class "Default")
      (node (ref "J6") (pin "IN") (pinfunction "IN_IN") (pintype "passive"))
      (node (ref "R35") (pin "2") (pinfunction "2_2") (pintype "passive"))
    )
    (net (code "80") (name "Net-(J7-PadIN)") (class "Default")
      (node (ref "J7") (pin "IN") (pinfunction "IN_IN") (pintype "passive"))
      (node (ref "R39") (pin "1") (pinfunction "1_1") (pintype "passive"))
    )
    (net (code "81") (name "Net-(J8-PadIN)") (class "Default")
      (node (ref "J8") (pin "IN") (pinfunction "IN_IN") (pintype "passive"))
      (node (ref "R41") (pin "1") (pinfunction "1_1") (pintype "passive"))
    )
    (net (code "82") (name "Net-(J9-PadIN)") (class "Default")
      (node (ref "J9") (pin "IN") (pinfunction "IN_IN") (pintype "passive"))
      (node (ref "R43") (pin "1") (pinfunction "1_1") (pintype "passive"))
    )
    (net (code "83") (name "Net-(J10-PadIN)") (class "Default")
      (node (ref "J10") (pin "IN") (pinfunction "IN_IN") (pintype "passive"))
      (node (ref "R45") (pin "1") (pinfunction "1_1") (pintype "passive"))
    )
    (net (code "84") (name "Net-(J11-PadIN)") (class "Default")
      (node (ref "J11") (pin "IN") (pinfunction "IN_IN") (pintype "passive"))
      (node (ref "R51") (pin "1") (pinfunction "1_1") (pintype "passive"))
    )
    (net (code "85") (name "Net-(J12-PadIN)") (class "Default")
      (node (ref "J12") (pin "IN") (pinfunction "IN_IN") (pintype "passive"))
      (node (ref "R53") (pin "1") (pinfunction "1_1") (pintype "passive"))
    )
    (net (code "86") (name "Net-(J13-PadIN)") (class "Default")
      (node (ref "J13") (pin "IN") (pinfunction "IN_IN") (pintype "passive"))
      (node (ref "R55") (pin "1") (pinfunction "1_1") (pintype "passive"))
    )
    (net (code "87") (name "Net-(J14-PadIN)") (class "Default")
      (node (ref "J14") (pin "IN") (pinfunction "IN_IN") (pintype "passive"))
      (node (ref "R57") (pin "1") (pinfunction "1_1") (pintype "passive"))
    )
    (net (code "88") (name "Net-(L1-PadA)") (class "Default")
      (node (ref "L1") (pin "A") (pinfunction "A_A") (pintype "passive"))
      (node (ref "R32") (pin "1") (pinfunction "1_1") (pintype "passive"))
    )
    (net (code "89") (name "Net-(P1-PadP$2)") (class "Default")
      (node (ref "P1") (pin "P$2") (pinfunction "P$2_P$2") (pintype "bidirectional"))
      (node (ref "R18") (pin "1") (pinfunction "1_1") (pintype "passive"))
    )
    (net (code "90") (name "Net-(P2-P$1)") (class "Default")
      (node (ref "P2") (pin "P1") (pinfunction "P$1_P1") (pintype "bidirectional"))
      (node (ref "R19") (pin "2") (pinfunction "2_2") (pintype "passive"))
    )
    (net (code "91") (name "Net-(P3-P$9-PadSDD{slash}MISO)") (class "Default")
      (node (ref "P3") (pin "SDD/MISO") (pinfunction "P$9_SDD/MISO") (pintype "bidirectional"))
      (node (ref "P3") (pin "SDD/MISO1") (pinfunction "P$9_SDD/MISO1") (pintype "bidirectional"))
      (node (ref "SJ1") (pin "1") (pinfunction "1_1") (pintype "passive"))
    )
    (net (code "92") (name "Net-(POT1A-A)") (class "Default")
      (node (ref "POT1") (pin "R1_1") (pinfunction "A_R1_1") (pintype "passive"))
      (node (ref "R8") (pin "1") (pinfunction "1_1") (pintype "passive"))
    )
    (net (code "93") (name "Net-(POT1B-A)") (class "Default")
      (node (ref "POT1") (pin "R2_1") (pinfunction "A_R2_1") (pintype "passive"))
      (node (ref "R9") (pin "1") (pinfunction "1_1") (pintype "passive"))
    )
    (net (code "94") (name "Net-(POT2-W)") (class "Default")
      (node (ref "POT2") (pin "2") (pinfunction "W_2") (pintype "passive"))
      (node (ref "R42") (pin "1") (pinfunction "1_1") (pintype "passive"))
    )
    (net (code "95") (name "Net-(POT3-W)") (class "Default")
      (node (ref "POT3") (pin "2") (pinfunction "W_2") (pintype "passive"))
      (node (ref "R44") (pin "1") (pinfunction "1_1") (pintype "passive"))
    )
    (net (code "96") (name "Net-(POT4-W)") (class "Default")
      (node (ref "POT4") (pin "2") (pinfunction "W_2") (pintype "passive"))
      (node (ref "R54") (pin "1") (pinfunction "1_1") (pintype "passive"))
    )
    (net (code "97") (name "Net-(POT5-W)") (class "Default")
      (node (ref "POT5") (pin "2") (pinfunction "W_2") (pintype "passive"))
      (node (ref "R56") (pin "1") (pinfunction "1_1") (pintype "passive"))
    )
    (net (code "98") (name "Net-(Q2-B)") (class "Default")
      (node (ref "Q2") (pin "1") (pinfunction "B_1") (pintype "passive"))
      (node (ref "R25") (pin "1") (pinfunction "1_1") (pintype "passive"))
    )
    (net (code "99") (name "Net-(Q3-B)") (class "Default")
      (node (ref "Q3") (pin "1") (pinfunction "B_1") (pintype "passive"))
      (node (ref "R26") (pin "1") (pinfunction "1_1") (pintype "passive"))
    )
    (net (code "100") (name "Net-(Q4-B)") (class "Default")
      (node (ref "Q4") (pin "1") (pinfunction "B_1") (pintype "passive"))
      (node (ref "R27") (pin "1") (pinfunction "1_1") (pintype "passive"))
    )
    (net (code "101") (name "Net-(Q5-B)") (class "Default")
      (node (ref "Q5") (pin "1") (pinfunction "B_1") (pintype "passive"))
      (node (ref "R34") (pin "1") (pinfunction "1_1") (pintype "passive"))
    )
    (net (code "102") (name "Net-(Q6-B)") (class "Default")
      (node (ref "Q6") (pin "1") (pinfunction "B_1") (pintype "passive"))
      (node (ref "R35") (pin "1") (pinfunction "1_1") (pintype "passive"))
    )
    (net (code "103") (name "RHPOUT") (class "Default")
      (node (ref "IC4") (pin "10") (pinfunction "RHPOUT_10") (pintype "bidirectional"))
    )
    (net (code "104") (name "RIN") (class "Default")
      (node (ref "C12") (pin "1") (pinfunction "1_1") (pintype "passive"))
      (node (ref "IC4") (pin "19") (pinfunction "RLINEIN_19") (pintype "bidirectional"))
    )
    (net (code "105") (name "ROUT") (class "Default")
      (node (ref "C2") (pin "2") (pinfunction "2_2") (pintype "passive"))
      (node (ref "IC4") (pin "13") (pinfunction "ROUT_13") (pintype "bidirectional"))
    )
    (net (code "106") (name "RTS") (class "Default")
      (node (ref "IC6") (pin "P$19") (pinfunction "P$19_P$19") (pintype "bidirectional"))
      (node (ref "Q2") (pin "2") (pinfunction "E_2") (pintype "passive"))
      (node (ref "R26") (pin "2") (pinfunction "2_2") (pintype "passive"))
      (node (ref "R27") (pin "2") (pinfunction "2_2") (pintype "passive"))
    )
    (net (code "107") (name "RXD") (class "Default")
      (node (ref "IC5") (pin "P$34") (pinfunction "P$34_P$34") (pintype "bidirectional"))
      (node (ref "IC6") (pin "P$21") (pinfunction "P$21_P$21") (pintype "bidirectional"))
    )
    (net (code "108") (name "TXD") (class "Default")
      (node (ref "IC5") (pin "P$35") (pinfunction "P$35_P$35") (pintype "bidirectional"))
      (node (ref "IC6") (pin "P$20") (pinfunction "P$20_P$20") (pintype "bidirectional"))
    )
    (net (code "109") (name "VN_IO39") (class "Default")
      (node (ref "C47") (pin "1") (pinfunction "1_1") (pintype "passive"))
      (node (ref "IC5") (pin "P$5") (pinfunction "P$5_P$5") (pintype "bidirectional"))
      (node (ref "Q5") (pin "3") (pinfunction "C_3") (pintype "passive"))
      (node (ref "R36") (pin "2") (pinfunction "2_2") (pintype "passive"))
      (node (ref "SW2") (pin "P$1") (pinfunction "1_P$1") (pintype "passive"))
      (node (ref "SW2") (pin "P$2") (pinfunction "2_P$2") (pintype "passive"))
    )
    (net (code "110") (name "VP_IO36") (class "Default")
      (node (ref "C48") (pin "1") (pinfunction "1_1") (pintype "passive"))
      (node (ref "IC5") (pin "P$4") (pinfunction "P$4_P$4") (pintype "bidirectional"))
      (node (ref "Q6") (pin "3") (pinfunction "C_3") (pintype "passive"))
      (node (ref "R37") (pin "2") (pinfunction "2_2") (pintype "passive"))
      (node (ref "SW3") (pin "P$1") (pinfunction "1_P$1") (pintype "passive"))
      (node (ref "SW3") (pin "P$2") (pinfunction "2_P$2") (pintype "passive"))
    )
    (net (code "111") (name "unconnected-(IC4-CLKOUT-Pad2)") (class "Default")
      (node (ref "IC4") (pin "2") (pinfunction "CLKOUT_2") (pintype "bidirectional"))
    )
    (net (code "112") (name "unconnected-(IC5-PadP$17)") (class "Default")
      (node (ref "IC5") (pin "P$17") (pinfunction "P$17_P$17") (pintype "bidirectional"))
    )
    (net (code "113") (name "unconnected-(IC5-PadP$18)") (class "Default")
      (node (ref "IC5") (pin "P$18") (pinfunction "P$18_P$18") (pintype "bidirectional"))
    )
    (net (code "114") (name "unconnected-(IC5-PadP$19)") (class "Default")
      (node (ref "IC5") (pin "P$19") (pinfunction "P$19_P$19") (pintype "bidirectional"))
    )
    (net (code "115") (name "unconnected-(IC5-PadP$20)") (class "Default")
      (node (ref "IC5") (pin "P$20") (pinfunction "P$20_P$20") (pintype "bidirectional"))
    )
    (net (code "116") (name "unconnected-(IC5-PadP$21)") (class "Default")
      (node (ref "IC5") (pin "P$21") (pinfunction "P$21_P$21") (pintype "bidirectional"))
    )
    (net (code "117") (name "unconnected-(IC5-PadP$22)") (class "Default")
      (node (ref "IC5") (pin "P$22") (pinfunction "P$22_P$22") (pintype "bidirectional"))
    )
    (net (code "118") (name "unconnected-(IC5-PadP$27)") (class "Default")
      (node (ref "IC5") (pin "P$27") (pinfunction "P$27_P$27") (pintype "bidirectional"))
    )
    (net (code "119") (name "unconnected-(IC5-PadP$28)") (class "Default")
      (node (ref "IC5") (pin "P$28") (pinfunction "P$28_P$28") (pintype "bidirectional"))
    )
    (net (code "120") (name "unconnected-(IC5-PadP$32)") (class "Default")
      (node (ref "IC5") (pin "P$32") (pinfunction "P$32_P$32") (pintype "bidirectional"))
    )
    (net (code "121") (name "unconnected-(IC6-PadP$1)") (class "Default")
      (node (ref "IC6") (pin "P$1") (pinfunction "P$1_P$1") (pintype "bidirectional"))
    )
    (net (code "122") (name "unconnected-(IC6-PadP$10)") (class "Default")
      (node (ref "IC6") (pin "P$10") (pinfunction "P$10_P$10") (pintype "bidirectional"))
    )
    (net (code "123") (name "unconnected-(IC6-PadP$11)") (class "Default")
      (node (ref "IC6") (pin "P$11") (pinfunction "P$11_P$11") (pintype "bidirectional"))
    )
    (net (code "124") (name "unconnected-(IC6-PadP$12)") (class "Default")
      (node (ref "IC6") (pin "P$12") (pinfunction "P$12_P$12") (pintype "bidirectional"))
    )
    (net (code "125") (name "unconnected-(IC6-PadP$13)") (class "Default")
      (node (ref "IC6") (pin "P$13") (pinfunction "P$13_P$13") (pintype "bidirectional"))
    )
    (net (code "126") (name "unconnected-(IC6-PadP$14)") (class "Default")
      (node (ref "IC6") (pin "P$14") (pinfunction "P$14_P$14") (pintype "bidirectional"))
    )
    (net (code "127") (name "unconnected-(IC6-PadP$15)") (class "Default")
      (node (ref "IC6") (pin "P$15") (pinfunction "P$15_P$15") (pintype "bidirectional"))
    )
    (net (code "128") (name "unconnected-(IC6-PadP$16)") (class "Default")
      (node (ref "IC6") (pin "P$16") (pinfunction "P$16_P$16") (pintype "bidirectional"))
    )
    (net (code "129") (name "unconnected-(IC6-PadP$17)") (class "Default")
      (node (ref "IC6") (pin "P$17") (pinfunction "P$17_P$17") (pintype "bidirectional"))
    )
    (net (code "130") (name "unconnected-(IC6-PadP$18)") (class "Default")
      (node (ref "IC6") (pin "P$18") (pinfunction "P$18_P$18") (pintype "bidirectional"))
    )
    (net (code "131") (name "unconnected-(IC6-PadP$22)") (class "Default")
      (node (ref "IC6") (pin "P$22") (pinfunction "P$22_P$22") (pintype "bidirectional"))
    )
    (net (code "132") (name "unconnected-(IC6-PadP$24)") (class "Default")
      (node (ref "IC6") (pin "P$24") (pinfunction "P$24_P$24") (pintype "bidirectional"))
    )
    (net (code "133") (name "unconnected-(J3-PadNORM)") (class "Default")
      (node (ref "J3") (pin "NORM") (pinfunction "NORM_NORM") (pintype "passive"))
    )
    (net (code "134") (name "unconnected-(J4-PadNORM)") (class "Default")
      (node (ref "J4") (pin "NORM") (pinfunction "NORM_NORM") (pintype "passive"))
    )
    (net (code "135") (name "unconnected-(P1-PadP$1)") (class "Default")
      (node (ref "P1") (pin "P$1") (pinfunction "P$1_P$1") (pintype "bidirectional"))
    )
    (net (code "136") (name "unconnected-(P1-PadP$8)") (class "Default")
      (node (ref "P1") (pin "P$8") (pinfunction "P$8_P$8") (pintype "bidirectional"))
    )
    (net (code "137") (name "unconnected-(P2-P$4-PadP4)") (class "Default")
      (node (ref "P2") (pin "P4") (pinfunction "P$4_P4") (pintype "bidirectional"))
    )
  )
)
